# sweet_sixteen_v24_3.net
KiCad netlist of a schematic drawn in EAGLE
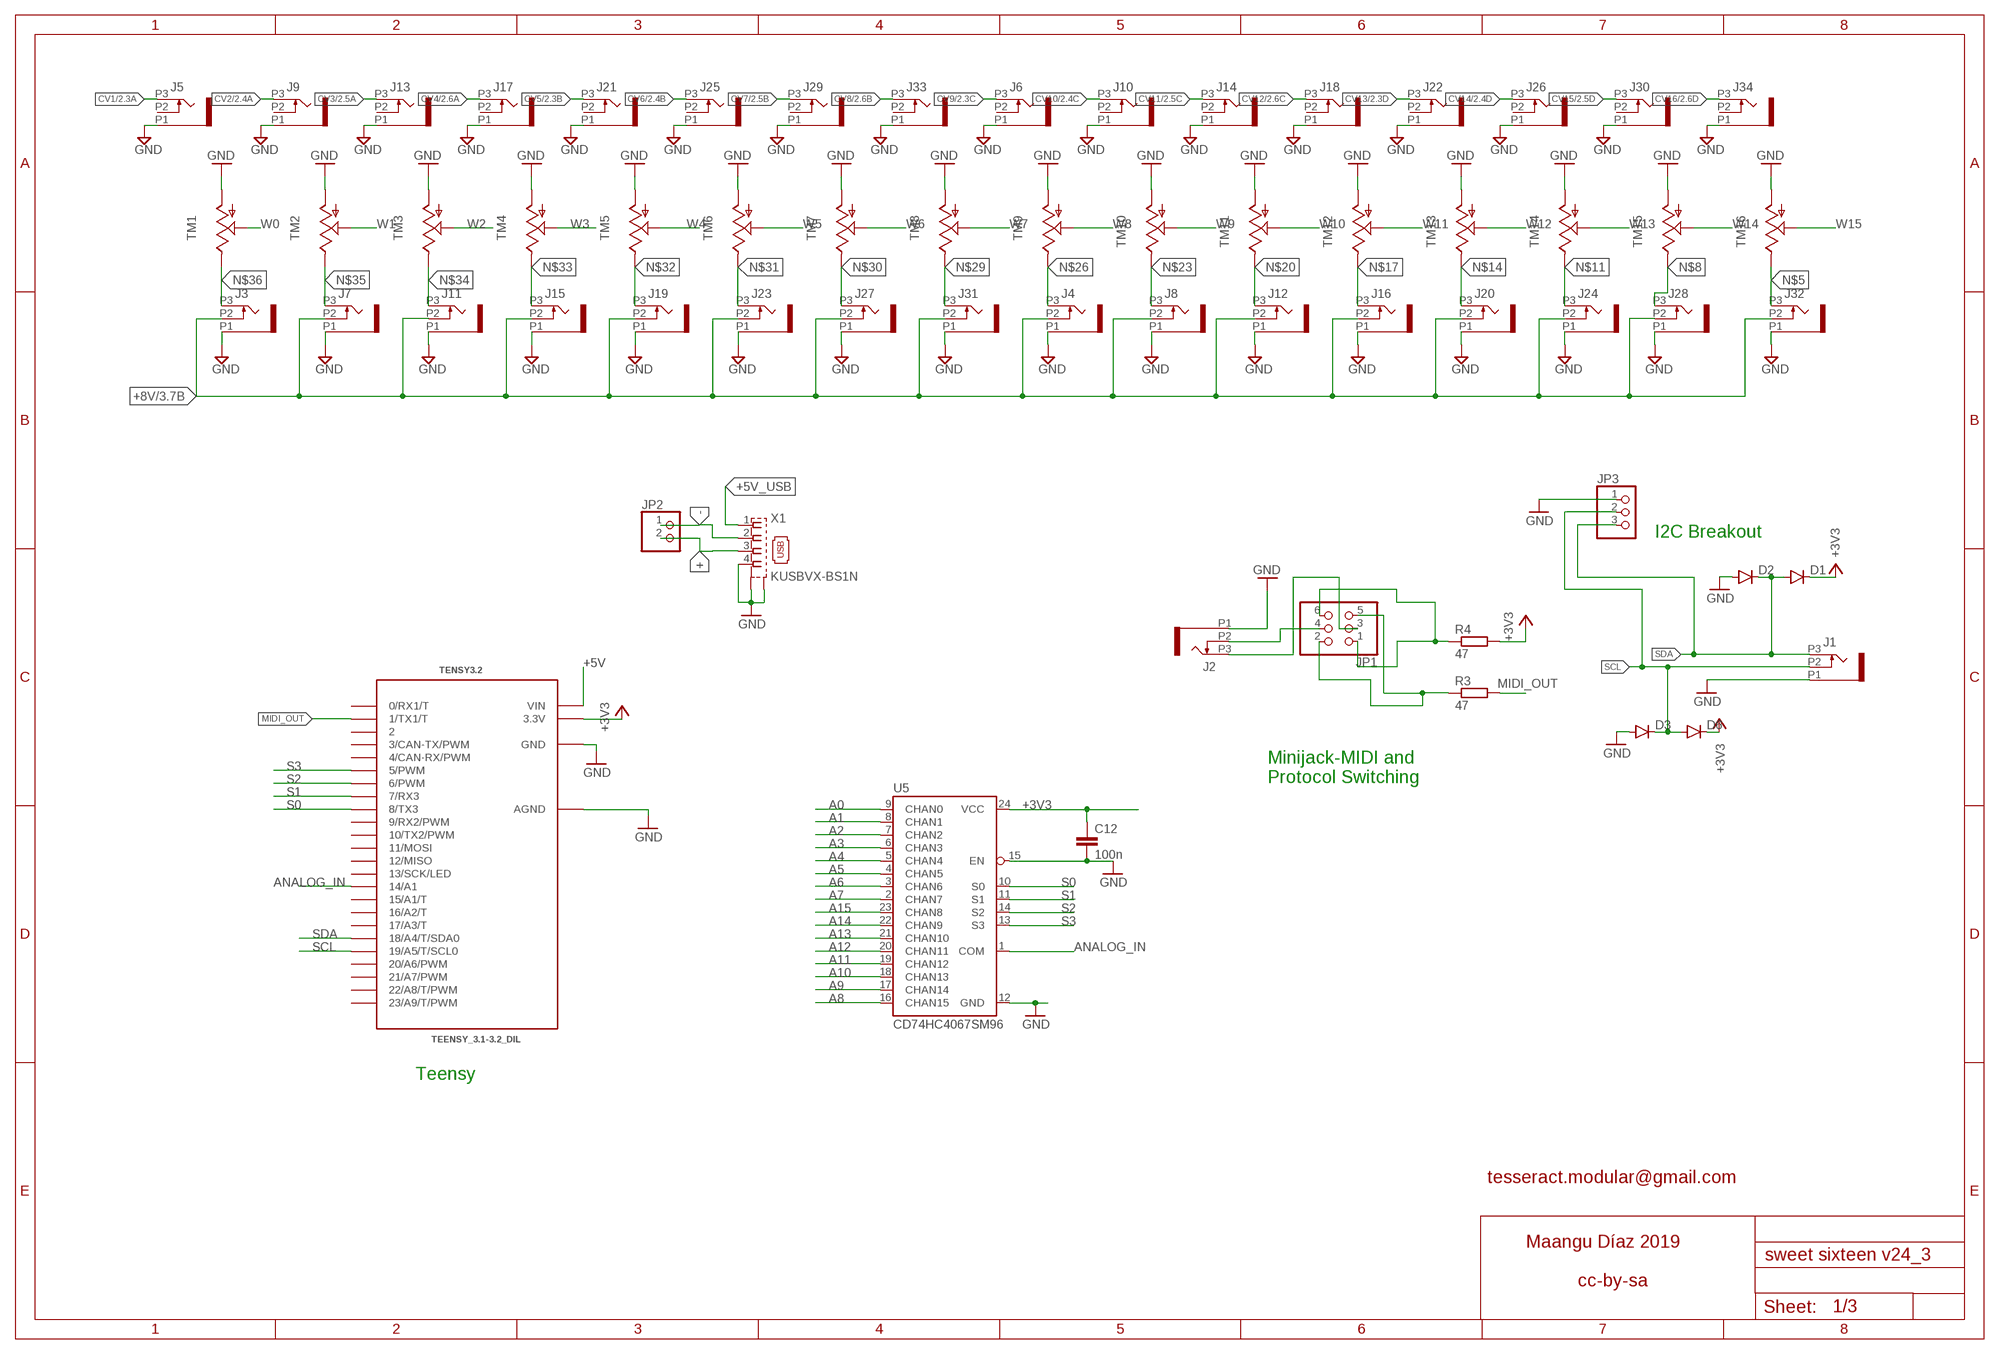
[diagram p0: schematic, sheet 1]
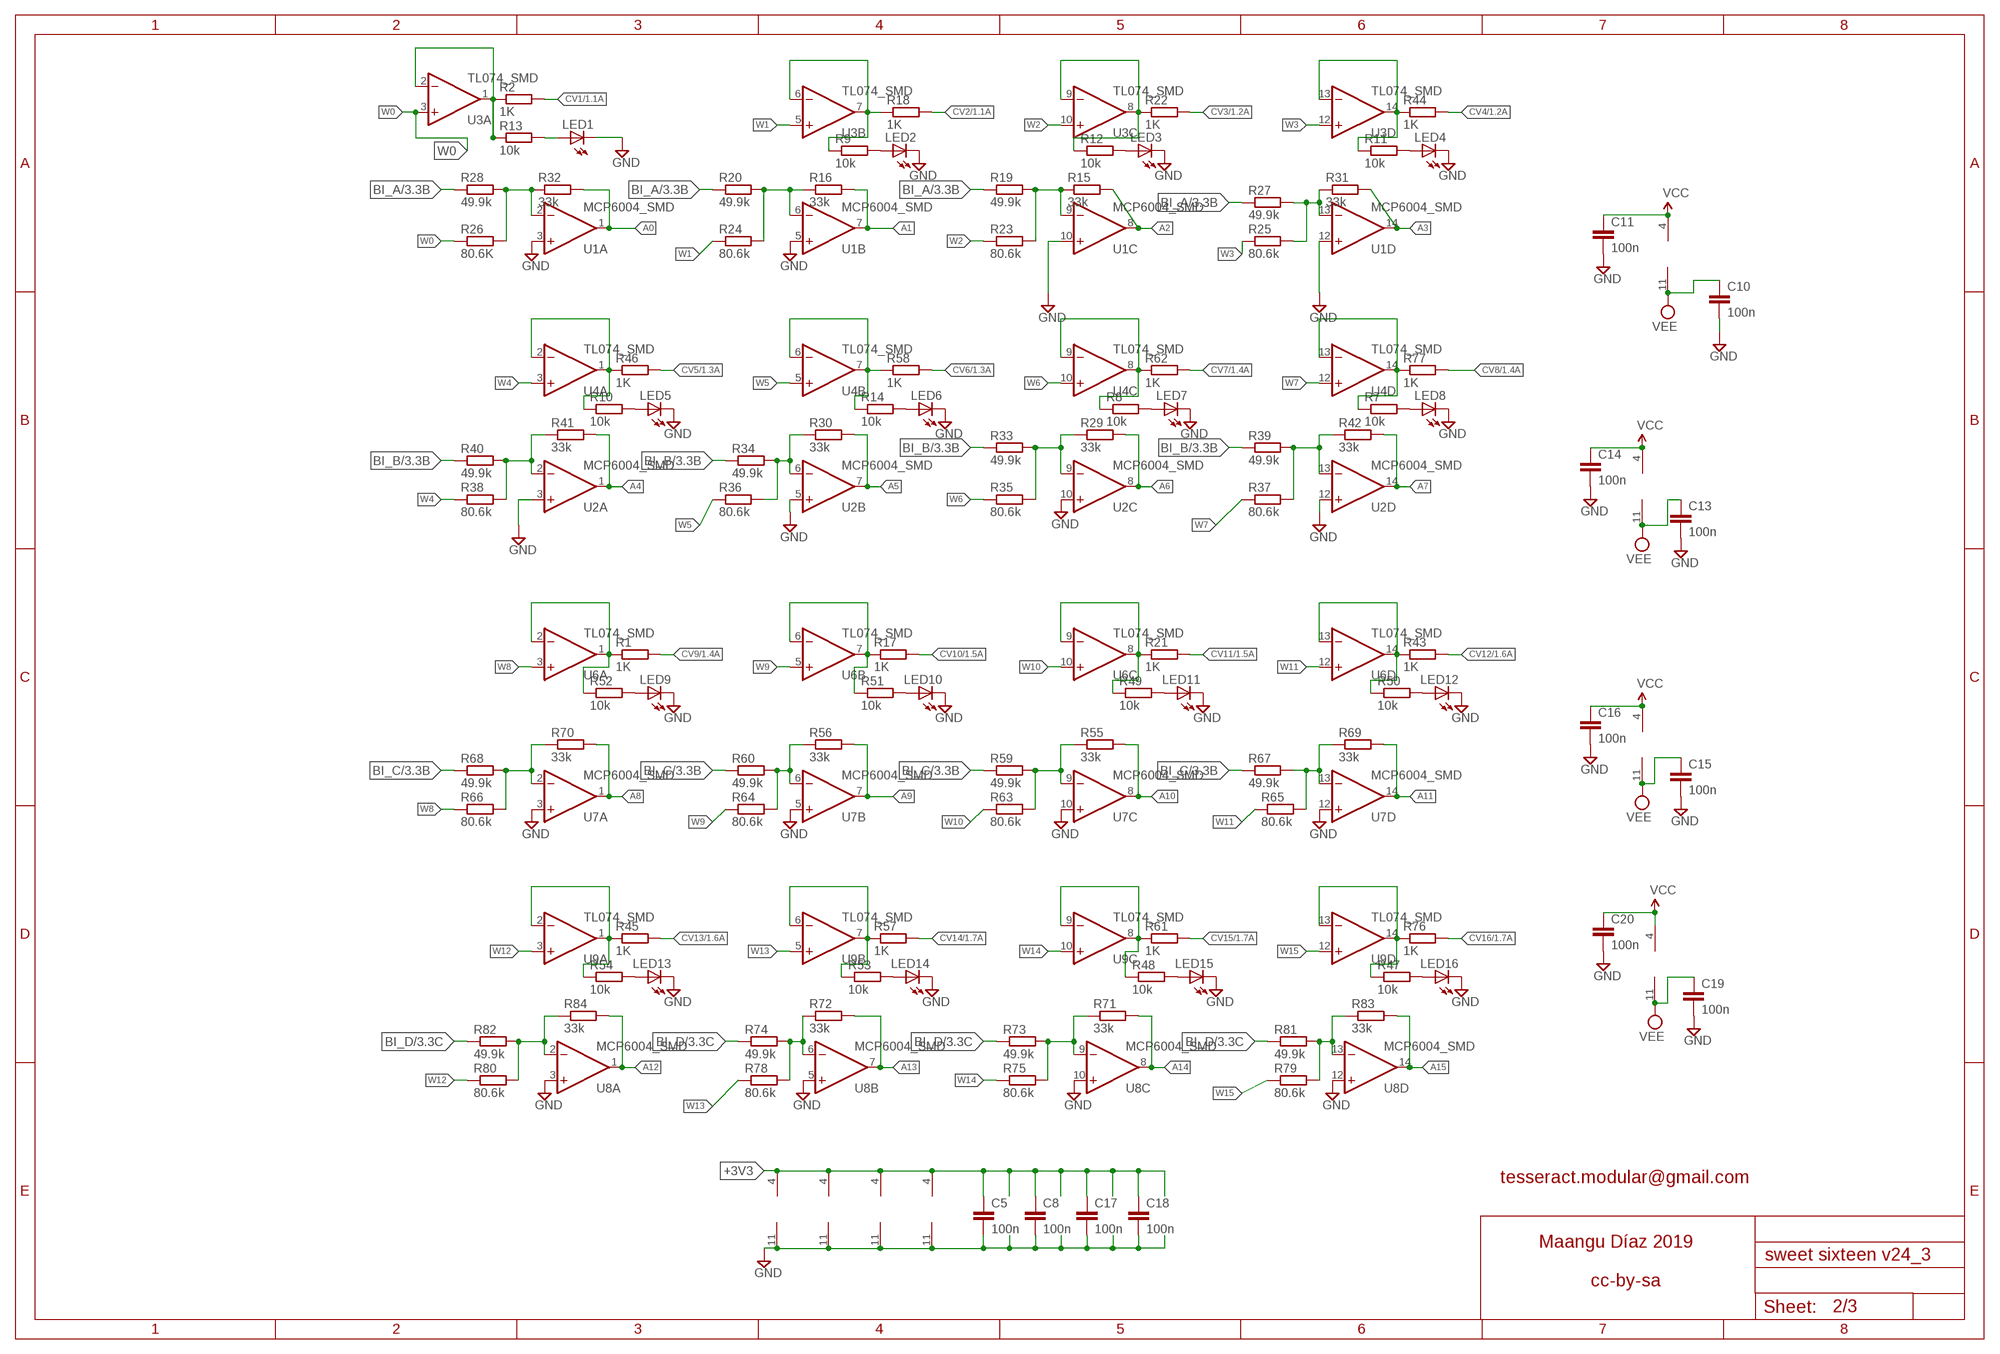
[diagram p1: schematic, sheet 2]
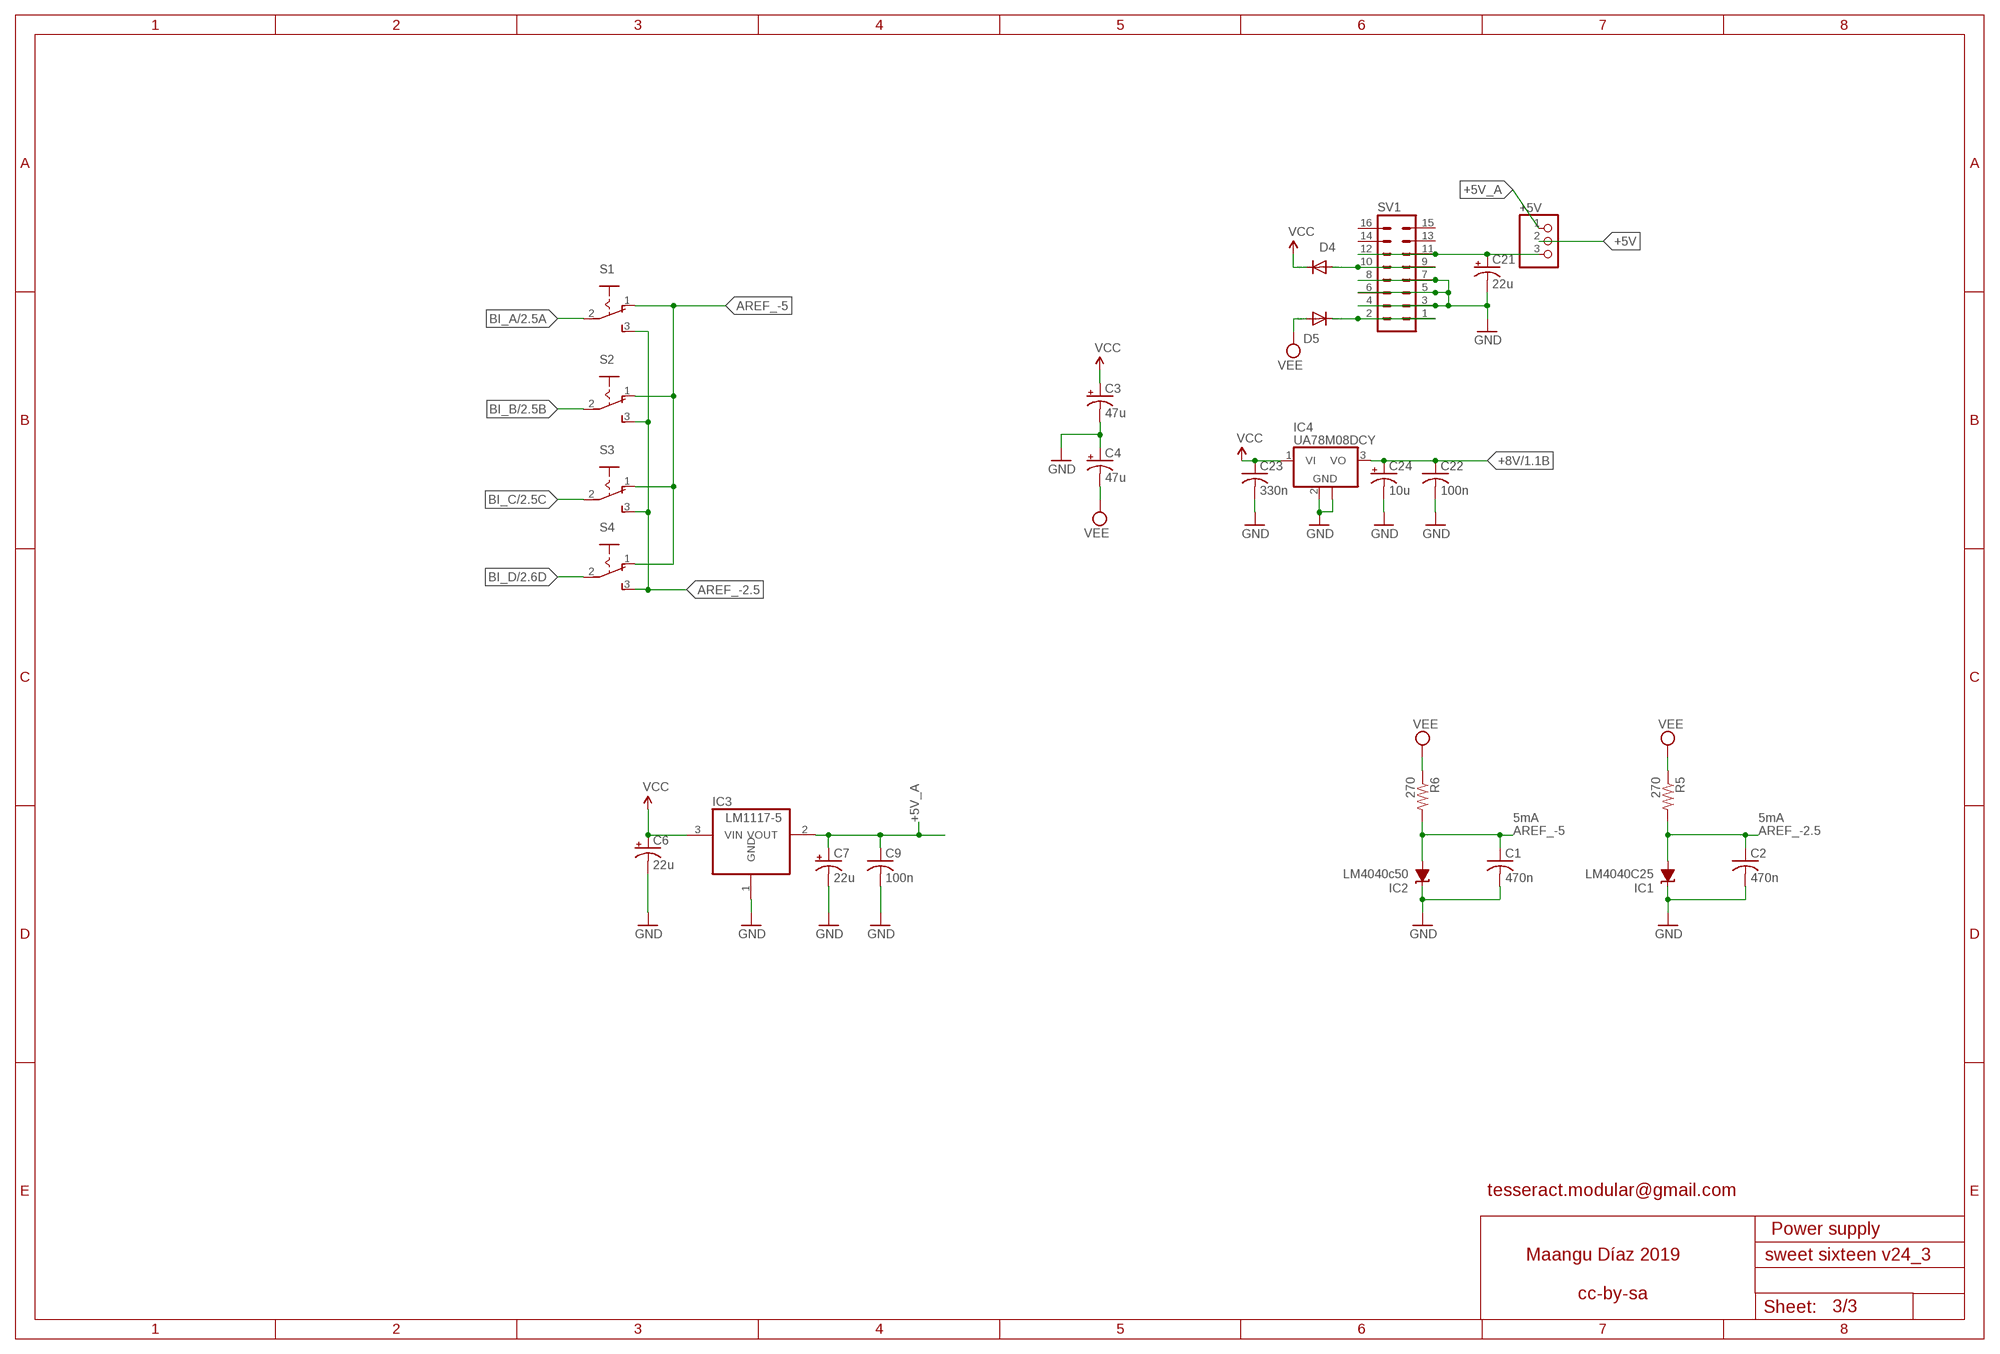
[diagram p2: schematic, sheet 3]

(export (version "E")
  (design (tool "Eeschema 10.0.6"))
  (components
    (comp (ref "+5V")
      (value "PINHD-1X3")
      (footprint "eagle-import:1X03")
      (libsource (lib "eagle-import") (part "PINHD-1X3"))
    )
    (comp (ref "C1")
      (value "470n")
      (footprint "eagle-import:C0603")
      (libsource (lib "eagle-import") (part "C-USC0603"))
    )
    (comp (ref "C2")
      (value "470n")
      (footprint "eagle-import:C0603")
      (libsource (lib "eagle-import") (part "C-USC0603"))
    )
    (comp (ref "C3")
      (value "47u")
      (footprint "eagle-import:PANASONIC_D")
      (libsource (lib "eagle-import") (part "CPOL-USD"))
    )
    (comp (ref "C4")
      (value "47u")
      (footprint "eagle-import:PANASONIC_D")
      (libsource (lib "eagle-import") (part "CPOL-USD"))
    )
    (comp (ref "C6")
      (value "22u")
      (footprint "eagle-import:PANASONIC_D")
      (libsource (lib "eagle-import") (part "CPOL-USD"))
    )
    (comp (ref "C7")
      (value "22u")
      (footprint "eagle-import:PANASONIC_D")
      (libsource (lib "eagle-import") (part "CPOL-USD"))
    )
    (comp (ref "C9")
      (value "100n")
      (footprint "eagle-import:C0603")
      (libsource (lib "eagle-import") (part "C-USC0603"))
    )
    (comp (ref "C21")
      (value "22u")
      (footprint "eagle-import:PANASONIC_D")
      (libsource (lib "eagle-import") (part "CPOL-USD"))
    )
    (comp (ref "C22")
      (value "100n")
      (footprint "eagle-import:C0603")
      (libsource (lib "eagle-import") (part "C-USC0603"))
    )
    (comp (ref "C23")
      (value "330n")
      (footprint "eagle-import:C0603")
      (libsource (lib "eagle-import") (part "C-USC0603"))
    )
    (comp (ref "C24")
      (value "10u")
      (footprint "eagle-import:PANASONIC_C")
      (libsource (lib "eagle-import") (part "CPOL-USC"))
    )
    (comp (ref "D4")
      (value "1N5819HW")
      (footprint "eagle-import:SOD123")
      (libsource (lib "eagle-import") (part "DIODE-SOD123"))
    )
    (comp (ref "D5")
      (value "1N5819HW")
      (footprint "eagle-import:SOD123")
      (libsource (lib "eagle-import") (part "DIODE-SOD123"))
    )
    (comp (ref "IC1")
      (value "LM4040C25")
      (footprint "eagle-import:DBZ_R-PDSO-G3")
      (fields (field (name "MPN") "LM4041B12IDBZR"))
      (libsource (lib "eagle-import") (part "LM4041DBZB12"))
    )
    (comp (ref "IC2")
      (value "LM4040c50")
      (footprint "eagle-import:DBZ_R-PDSO-G3")
      (fields (field (name "MPN") "LM4041B12IDBZR"))
      (libsource (lib "eagle-import") (part "LM4041DBZB12"))
    )
    (comp (ref "IC3")
      (value "LM1117-5")
      (footprint "eagle-import:SOT223")
      (libsource (lib "eagle-import") (part "REG1117"))
    )
    (comp (ref "IC4")
      (value "UA78M08DCY")
      (footprint "eagle-import:SOT223")
      (libsource (lib "eagle-import") (part "UA78MDCY08"))
    )
    (comp (ref "R5")
      (value "270")
      (footprint "eagle-import:R0603")
      (libsource (lib "eagle-import") (part "R-US_R0603"))
    )
    (comp (ref "R6")
      (value "270")
      (footprint "eagle-import:R0603")
      (libsource (lib "eagle-import") (part "R-US_R0603"))
    )
    (comp (ref "S1")
      (value "255SB-MANGURRIN")
      (footprint "eagle-import:255SB_MANGU")
      (libsource (lib "eagle-import") (part "255SB-MANGURRIN"))
    )
    (comp (ref "S2")
      (value "255SB-MANGURRIN")
      (footprint "eagle-import:255SB_MANGU")
      (libsource (lib "eagle-import") (part "255SB-MANGURRIN"))
    )
    (comp (ref "S3")
      (value "255SB-MANGURRIN")
      (footprint "eagle-import:255SB_MANGU")
      (libsource (lib "eagle-import") (part "255SB-MANGURRIN"))
    )
    (comp (ref "S4")
      (value "255SB-MANGURRIN")
      (footprint "eagle-import:255SB_MANGU")
      (libsource (lib "eagle-import") (part "255SB-MANGURRIN"))
    )
    (comp (ref "SV1")
      (value "ML16")
      (footprint "eagle-import:ML16")
      (libsource (lib "eagle-import") (part "ML16"))
    )
    (comp (ref "C12")
      (value "100n")
      (footprint "eagle-import:C0603")
      (libsource (lib "eagle-import") (part "C-EUC0603"))
    )
    (comp (ref "D1")
      (value "DIODESOD123")
      (footprint "eagle-import:SOD-123")
      (libsource (lib "eagle-import") (part "DIODESOD123"))
    )
    (comp (ref "D2")
      (value "DIODESOD123")
      (footprint "eagle-import:SOD-123")
      (libsource (lib "eagle-import") (part "DIODESOD123"))
    )
    (comp (ref "D3")
      (value "DIODESOD123")
      (footprint "eagle-import:SOD-123")
      (libsource (lib "eagle-import") (part "DIODESOD123"))
    )
    (comp (ref "D6")
      (value "DIODESOD123")
      (footprint "eagle-import:SOD-123")
      (libsource (lib "eagle-import") (part "DIODESOD123"))
    )
    (comp (ref "J1")
      (value "PJ301_THONKICONN6")
      (footprint "eagle-import:WQP_PJ_301M6")
      (libsource (lib "eagle-import") (part "PJ301_THONKICONN6"))
    )
    (comp (ref "J2")
      (value "PJ301_THONKICONN6")
      (footprint "eagle-import:WQP_PJ_301M6")
      (libsource (lib "eagle-import") (part "PJ301_THONKICONN6"))
    )
    (comp (ref "J3")
      (value "PJ301_THONKICONN6")
      (footprint "eagle-import:WQP_PJ_301M6")
      (libsource (lib "eagle-import") (part "PJ301_THONKICONN6"))
    )
    (comp (ref "J4")
      (value "PJ301_THONKICONN6")
      (footprint "eagle-import:WQP_PJ_301M6")
      (libsource (lib "eagle-import") (part "PJ301_THONKICONN6"))
    )
    (comp (ref "J5")
      (value "PJ301_THONKICONN6")
      (footprint "eagle-import:WQP_PJ_301M6")
      (libsource (lib "eagle-import") (part "PJ301_THONKICONN6"))
    )
    (comp (ref "J6")
      (value "PJ301_THONKICONN6")
      (footprint "eagle-import:WQP_PJ_301M6")
      (libsource (lib "eagle-import") (part "PJ301_THONKICONN6"))
    )
    (comp (ref "J7")
      (value "PJ301_THONKICONN6")
      (footprint "eagle-import:WQP_PJ_301M6")
      (libsource (lib "eagle-import") (part "PJ301_THONKICONN6"))
    )
    (comp (ref "J8")
      (value "PJ301_THONKICONN6")
      (footprint "eagle-import:WQP_PJ_301M6")
      (libsource (lib "eagle-import") (part "PJ301_THONKICONN6"))
    )
    (comp (ref "J9")
      (value "PJ301_THONKICONN6")
      (footprint "eagle-import:WQP_PJ_301M6")
      (libsource (lib "eagle-import") (part "PJ301_THONKICONN6"))
    )
    (comp (ref "J10")
      (value "PJ301_THONKICONN6")
      (footprint "eagle-import:WQP_PJ_301M6")
      (libsource (lib "eagle-import") (part "PJ301_THONKICONN6"))
    )
    (comp (ref "J11")
      (value "PJ301_THONKICONN6")
      (footprint "eagle-import:WQP_PJ_301M6")
      (libsource (lib "eagle-import") (part "PJ301_THONKICONN6"))
    )
    (comp (ref "J12")
      (value "PJ301_THONKICONN6")
      (footprint "eagle-import:WQP_PJ_301M6")
      (libsource (lib "eagle-import") (part "PJ301_THONKICONN6"))
    )
    (comp (ref "J13")
      (value "PJ301_THONKICONN6")
      (footprint "eagle-import:WQP_PJ_301M6")
      (libsource (lib "eagle-import") (part "PJ301_THONKICONN6"))
    )
    (comp (ref "J14")
      (value "PJ301_THONKICONN6")
      (footprint "eagle-import:WQP_PJ_301M6")
      (libsource (lib "eagle-import") (part "PJ301_THONKICONN6"))
    )
    (comp (ref "J15")
      (value "PJ301_THONKICONN6")
      (footprint "eagle-import:WQP_PJ_301M6")
      (libsource (lib "eagle-import") (part "PJ301_THONKICONN6"))
    )
    (comp (ref "J16")
      (value "PJ301_THONKICONN6")
      (footprint "eagle-import:WQP_PJ_301M6")
      (libsource (lib "eagle-import") (part "PJ301_THONKICONN6"))
    )
    (comp (ref "J17")
      (value "PJ301_THONKICONN6")
      (footprint "eagle-import:WQP_PJ_301M6")
      (libsource (lib "eagle-import") (part "PJ301_THONKICONN6"))
    )
    (comp (ref "J18")
      (value "PJ301_THONKICONN6")
      (footprint "eagle-import:WQP_PJ_301M6")
      (libsource (lib "eagle-import") (part "PJ301_THONKICONN6"))
    )
    (comp (ref "J19")
      (value "PJ301_THONKICONN6")
      (footprint "eagle-import:WQP_PJ_301M6")
      (libsource (lib "eagle-import") (part "PJ301_THONKICONN6"))
    )
    (comp (ref "J20")
      (value "PJ301_THONKICONN6")
      (footprint "eagle-import:WQP_PJ_301M6")
      (libsource (lib "eagle-import") (part "PJ301_THONKICONN6"))
    )
    (comp (ref "J21")
      (value "PJ301_THONKICONN6")
      (footprint "eagle-import:WQP_PJ_301M6")
      (libsource (lib "eagle-import") (part "PJ301_THONKICONN6"))
    )
    (comp (ref "J22")
      (value "PJ301_THONKICONN6")
      (footprint "eagle-import:WQP_PJ_301M6")
      (libsource (lib "eagle-import") (part "PJ301_THONKICONN6"))
    )
    (comp (ref "J23")
      (value "PJ301_THONKICONN6")
      (footprint "eagle-import:WQP_PJ_301M6")
      (libsource (lib "eagle-import") (part "PJ301_THONKICONN6"))
    )
    (comp (ref "J24")
      (value "PJ301_THONKICONN6")
      (footprint "eagle-import:WQP_PJ_301M6")
      (libsource (lib "eagle-import") (part "PJ301_THONKICONN6"))
    )
    (comp (ref "J25")
      (value "PJ301_THONKICONN6")
      (footprint "eagle-import:WQP_PJ_301M6")
      (libsource (lib "eagle-import") (part "PJ301_THONKICONN6"))
    )
    (comp (ref "J26")
      (value "PJ301_THONKICONN6")
      (footprint "eagle-import:WQP_PJ_301M6")
      (libsource (lib "eagle-import") (part "PJ301_THONKICONN6"))
    )
    (comp (ref "J27")
      (value "PJ301_THONKICONN6")
      (footprint "eagle-import:WQP_PJ_301M6")
      (libsource (lib "eagle-import") (part "PJ301_THONKICONN6"))
    )
    (comp (ref "J28")
      (value "PJ301_THONKICONN6")
      (footprint "eagle-import:WQP_PJ_301M6")
      (libsource (lib "eagle-import") (part "PJ301_THONKICONN6"))
    )
    (comp (ref "J29")
      (value "PJ301_THONKICONN6")
      (footprint "eagle-import:WQP_PJ_301M6")
      (libsource (lib "eagle-import") (part "PJ301_THONKICONN6"))
    )
    (comp (ref "J30")
      (value "PJ301_THONKICONN6")
      (footprint "eagle-import:WQP_PJ_301M6")
      (libsource (lib "eagle-import") (part "PJ301_THONKICONN6"))
    )
    (comp (ref "J31")
      (value "PJ301_THONKICONN6")
      (footprint "eagle-import:WQP_PJ_301M6")
      (libsource (lib "eagle-import") (part "PJ301_THONKICONN6"))
    )
    (comp (ref "J32")
      (value "PJ301_THONKICONN6")
      (footprint "eagle-import:WQP_PJ_301M6")
      (libsource (lib "eagle-import") (part "PJ301_THONKICONN6"))
    )
    (comp (ref "J33")
      (value "PJ301_THONKICONN6")
      (footprint "eagle-import:WQP_PJ_301M6")
      (libsource (lib "eagle-import") (part "PJ301_THONKICONN6"))
    )
    (comp (ref "J34")
      (value "PJ301_THONKICONN6")
      (footprint "eagle-import:WQP_PJ_301M6")
      (libsource (lib "eagle-import") (part "PJ301_THONKICONN6"))
    )
    (comp (ref "JP1")
      (value "PINHD-2X3")
      (footprint "eagle-import:2X03")
      (libsource (lib "eagle-import") (part "PINHD-2X3"))
    )
    (comp (ref "JP2")
      (value "PINHD-1X2")
      (footprint "eagle-import:1X02")
      (libsource (lib "eagle-import") (part "PINHD-1X2"))
    )
    (comp (ref "JP3")
      (value "PINHD-1X3")
      (footprint "eagle-import:1X03")
      (libsource (lib "eagle-import") (part "PINHD-1X3"))
    )
    (comp (ref "R3")
      (value "47")
      (footprint "eagle-import:R0805")
      (libsource (lib "eagle-import") (part "R-EU_R0805"))
    )
    (comp (ref "R4")
      (value "47")
      (footprint "eagle-import:R0805")
      (libsource (lib "eagle-import") (part "R-EU_R0805"))
    )
    (comp (ref "TENSY3.2")
      (value "TEENSY_3.1-3.2_DIL")
      (footprint "eagle-import:TEENSY_3.0-3.2&LC_DIL")
      (libsource (lib "eagle-import") (part "TEENSY_3.1-3.2_DIL"))
    )
    (comp (ref "TM1")
      (value "TRIMSLIDE45")
      (footprint "eagle-import:SLIDEPOT-45")
      (libsource (lib "eagle-import") (part "TRIMSLIDE45"))
    )
    (comp (ref "TM2")
      (value "TRIMSLIDE45")
      (footprint "eagle-import:SLIDEPOT-45")
      (libsource (lib "eagle-import") (part "TRIMSLIDE45"))
    )
    (comp (ref "TM3")
      (value "TRIMSLIDE45")
      (footprint "eagle-import:SLIDEPOT-45")
      (libsource (lib "eagle-import") (part "TRIMSLIDE45"))
    )
    (comp (ref "TM4")
      (value "TRIMSLIDE45")
      (footprint "eagle-import:SLIDEPOT-45")
      (libsource (lib "eagle-import") (part "TRIMSLIDE45"))
    )
    (comp (ref "TM5")
      (value "TRIMSLIDE45")
      (footprint "eagle-import:SLIDEPOT-45")
      (libsource (lib "eagle-import") (part "TRIMSLIDE45"))
    )
    (comp (ref "TM6")
      (value "TRIMSLIDE45")
      (footprint "eagle-import:SLIDEPOT-45")
      (libsource (lib "eagle-import") (part "TRIMSLIDE45"))
    )
    (comp (ref "TM7")
      (value "TRIMSLIDE45")
      (footprint "eagle-import:SLIDEPOT-45")
      (libsource (lib "eagle-import") (part "TRIMSLIDE45"))
    )
    (comp (ref "TM8")
      (value "TRIMSLIDE45")
      (footprint "eagle-import:SLIDEPOT-45")
      (libsource (lib "eagle-import") (part "TRIMSLIDE45"))
    )
    (comp (ref "TM9")
      (value "TRIMSLIDE45")
      (footprint "eagle-import:SLIDEPOT-45")
      (libsource (lib "eagle-import") (part "TRIMSLIDE45"))
    )
    (comp (ref "TM10")
      (value "TRIMSLIDE45")
      (footprint "eagle-import:SLIDEPOT-45")
      (libsource (lib "eagle-import") (part "TRIMSLIDE45"))
    )
    (comp (ref "TM11")
      (value "TRIMSLIDE45")
      (footprint "eagle-import:SLIDEPOT-45")
      (libsource (lib "eagle-import") (part "TRIMSLIDE45"))
    )
    (comp (ref "TM12")
      (value "TRIMSLIDE45")
      (footprint "eagle-import:SLIDEPOT-45")
      (libsource (lib "eagle-import") (part "TRIMSLIDE45"))
    )
    (comp (ref "TM13")
      (value "TRIMSLIDE45")
      (footprint "eagle-import:SLIDEPOT-45")
      (libsource (lib "eagle-import") (part "TRIMSLIDE45"))
    )
    (comp (ref "TM14")
      (value "TRIMSLIDE45")
      (footprint "eagle-import:SLIDEPOT-45")
      (libsource (lib "eagle-import") (part "TRIMSLIDE45"))
    )
    (comp (ref "TM15")
      (value "TRIMSLIDE45")
      (footprint "eagle-import:SLIDEPOT-45")
      (libsource (lib "eagle-import") (part "TRIMSLIDE45"))
    )
    (comp (ref "TM16")
      (value "TRIMSLIDE45")
      (footprint "eagle-import:SLIDEPOT-45")
      (libsource (lib "eagle-import") (part "TRIMSLIDE45"))
    )
    (comp (ref "U5")
      (value "CD74HC4067SM96")
      (footprint "eagle-import:SOIC127P1030X265-24")
      (libsource (lib "eagle-import") (part "744067SO24"))
    )
    (comp (ref "X1")
      (value "KUSBVX-BS1N")
      (footprint "eagle-import:KUSBVX-BS1N")
      (libsource (lib "eagle-import") (part "KUSBVX-BS1N"))
    )
    (comp (ref "C5")
      (value "100n")
      (footprint "eagle-import:C0603")
      (libsource (lib "eagle-import") (part "C-EUC0603"))
    )
    (comp (ref "C8")
      (value "100n")
      (footprint "eagle-import:C0603K")
      (libsource (lib "eagle-import") (part "C-EUC0603K"))
    )
    (comp (ref "C10")
      (value "100n")
      (footprint "eagle-import:C0603")
      (libsource (lib "eagle-import") (part "C-EUC0603"))
    )
    (comp (ref "C11")
      (value "100n")
      (footprint "eagle-import:C0603")
      (libsource (lib "eagle-import") (part "C-EUC0603"))
    )
    (comp (ref "C13")
      (value "100n")
      (footprint "eagle-import:C0603")
      (libsource (lib "eagle-import") (part "C-EUC0603"))
    )
    (comp (ref "C14")
      (value "100n")
      (footprint "eagle-import:C0603")
      (libsource (lib "eagle-import") (part "C-EUC0603"))
    )
    (comp (ref "C15")
      (value "100n")
      (footprint "eagle-import:C0603")
      (libsource (lib "eagle-import") (part "C-EUC0603"))
    )
    (comp (ref "C16")
      (value "100n")
      (footprint "eagle-import:C0603")
      (libsource (lib "eagle-import") (part "C-EUC0603"))
    )
    (comp (ref "C17")
      (value "100n")
      (footprint "eagle-import:C0603K")
      (libsource (lib "eagle-import") (part "C-EUC0603K"))
    )
    (comp (ref "C18")
      (value "100n")
      (footprint "eagle-import:C0603")
      (libsource (lib "eagle-import") (part "C-EUC0603"))
    )
    (comp (ref "C19")
      (value "100n")
      (footprint "eagle-import:C0603")
      (libsource (lib "eagle-import") (part "C-EUC0603"))
    )
    (comp (ref "C20")
      (value "100n")
      (footprint "eagle-import:C0603")
      (libsource (lib "eagle-import") (part "C-EUC0603"))
    )
    (comp (ref "LED1")
      (value "LED3MM")
      (footprint "eagle-import:LED3MM")
      (libsource (lib "eagle-import") (part "LED3MM"))
    )
    (comp (ref "LED2")
      (value "LED3MM")
      (footprint "eagle-import:LED3MM")
      (libsource (lib "eagle-import") (part "LED3MM"))
    )
    (comp (ref "LED3")
      (value "LED3MM")
      (footprint "eagle-import:LED3MM")
      (libsource (lib "eagle-import") (part "LED3MM"))
    )
    (comp (ref "LED4")
      (value "LED3MM")
      (footprint "eagle-import:LED3MM")
      (libsource (lib "eagle-import") (part "LED3MM"))
    )
    (comp (ref "LED5")
      (value "LED3MM")
      (footprint "eagle-import:LED3MM")
      (libsource (lib "eagle-import") (part "LED3MM"))
    )
    (comp (ref "LED6")
      (value "LED3MM")
      (footprint "eagle-import:LED3MM")
      (libsource (lib "eagle-import") (part "LED3MM"))
    )
    (comp (ref "LED7")
      (value "LED3MM")
      (footprint "eagle-import:LED3MM")
      (libsource (lib "eagle-import") (part "LED3MM"))
    )
    (comp (ref "LED8")
      (value "LED3MM")
      (footprint "eagle-import:LED3MM")
      (libsource (lib "eagle-import") (part "LED3MM"))
    )
    (comp (ref "LED9")
      (value "LED3MM")
      (footprint "eagle-import:LED3MM")
      (libsource (lib "eagle-import") (part "LED3MM"))
    )
    (comp (ref "LED10")
      (value "LED3MM")
      (footprint "eagle-import:LED3MM")
      (libsource (lib "eagle-import") (part "LED3MM"))
    )
    (comp (ref "LED11")
      (value "LED3MM")
      (footprint "eagle-import:LED3MM")
      (libsource (lib "eagle-import") (part "LED3MM"))
    )
    (comp (ref "LED12")
      (value "LED3MM")
      (footprint "eagle-import:LED3MM")
      (libsource (lib "eagle-import") (part "LED3MM"))
    )
    (comp (ref "LED13")
      (value "LED3MM")
      (footprint "eagle-import:LED3MM")
      (libsource (lib "eagle-import") (part "LED3MM"))
    )
    (comp (ref "LED14")
      (value "LED3MM")
      (footprint "eagle-import:LED3MM")
      (libsource (lib "eagle-import") (part "LED3MM"))
    )
    (comp (ref "LED15")
      (value "LED3MM")
      (footprint "eagle-import:LED3MM")
      (libsource (lib "eagle-import") (part "LED3MM"))
    )
    (comp (ref "LED16")
      (value "LED3MM")
      (footprint "eagle-import:LED3MM")
      (libsource (lib "eagle-import") (part "LED3MM"))
    )
    (comp (ref "R1")
      (value "1K")
      (footprint "eagle-import:R0603")
      (libsource (lib "eagle-import") (part "R-EU_R0603"))
    )
    (comp (ref "R2")
      (value "1K")
      (footprint "eagle-import:R0603")
      (libsource (lib "eagle-import") (part "R-EU_R0603"))
    )
    (comp (ref "R7")
      (value "10k")
      (footprint "eagle-import:R0603")
      (libsource (lib "eagle-import") (part "R-EU_R0603"))
    )
    (comp (ref "R8")
      (value "10k")
      (footprint "eagle-import:R0603")
      (libsource (lib "eagle-import") (part "R-EU_R0603"))
    )
    (comp (ref "R9")
      (value "10k")
      (footprint "eagle-import:R0603")
      (libsource (lib "eagle-import") (part "R-EU_R0603"))
    )
    (comp (ref "R10")
      (value "10k")
      (footprint "eagle-import:R0603")
      (libsource (lib "eagle-import") (part "R-EU_R0603"))
    )
    (comp (ref "R11")
      (value "10k")
      (footprint "eagle-import:R0603")
      (libsource (lib "eagle-import") (part "R-EU_R0603"))
    )
    (comp (ref "R12")
      (value "10k")
      (footprint "eagle-import:R0603")
      (libsource (lib "eagle-import") (part "R-EU_R0603"))
    )
    (comp (ref "R13")
      (value "10k")
      (footprint "eagle-import:R0603")
      (libsource (lib "eagle-import") (part "R-EU_R0603"))
    )
    (comp (ref "R14")
      (value "10k")
      (footprint "eagle-import:R0603")
      (libsource (lib "eagle-import") (part "R-EU_R0603"))
    )
    (comp (ref "R15")
      (value "33k")
      (footprint "eagle-import:R0603")
      (libsource (lib "eagle-import") (part "R-EU_R0603"))
    )
    (comp (ref "R16")
      (value "33k")
      (footprint "eagle-import:R0603")
      (libsource (lib "eagle-import") (part "R-EU_R0603"))
    )
    (comp (ref "R17")
      (value "1K")
      (footprint "eagle-import:R0603")
      (libsource (lib "eagle-import") (part "R-EU_R0603"))
    )
    (comp (ref "R18")
      (value "1K")
      (footprint "eagle-import:R0603")
      (libsource (lib "eagle-import") (part "R-EU_R0603"))
    )
    (comp (ref "R19")
      (value "49.9k")
      (footprint "eagle-import:R0603")
      (libsource (lib "eagle-import") (part "R-EU_R0603"))
    )
    (comp (ref "R20")
      (value "49.9k")
      (footprint "eagle-import:R0603")
      (libsource (lib "eagle-import") (part "R-EU_R0603"))
    )
    (comp (ref "R21")
      (value "1K")
      (footprint "eagle-import:R0603")
      (libsource (lib "eagle-import") (part "R-EU_R0603"))
    )
    (comp (ref "R22")
      (value "1K")
      (footprint "eagle-import:R0603")
      (libsource (lib "eagle-import") (part "R-EU_R0603"))
    )
    (comp (ref "R23")
      (value "80.6k")
      (footprint "eagle-import:R0603")
      (libsource (lib "eagle-import") (part "R-EU_R0603"))
    )
    (comp (ref "R24")
      (value "80.6k")
      (footprint "eagle-import:R0603")
      (libsource (lib "eagle-import") (part "R-EU_R0603"))
    )
    (comp (ref "R25")
      (value "80.6k")
      (footprint "eagle-import:R0603")
      (libsource (lib "eagle-import") (part "R-EU_R0603"))
    )
    (comp (ref "R26")
      (value "80.6K")
      (footprint "eagle-import:R0603")
      (libsource (lib "eagle-import") (part "R-EU_R0603"))
    )
    (comp (ref "R27")
      (value "49.9k")
      (footprint "eagle-import:R0603")
      (libsource (lib "eagle-import") (part "R-EU_R0603"))
    )
    (comp (ref "R28")
      (value "49.9k")
      (footprint "eagle-import:R0603")
      (libsource (lib "eagle-import") (part "R-EU_R0603"))
    )
    (comp (ref "R29")
      (value "33k")
      (footprint "eagle-import:R0603")
      (libsource (lib "eagle-import") (part "R-EU_R0603"))
    )
    (comp (ref "R30")
      (value "33k")
      (footprint "eagle-import:R0603")
      (libsource (lib "eagle-import") (part "R-EU_R0603"))
    )
    (comp (ref "R31")
      (value "33k")
      (footprint "eagle-import:R0603")
      (libsource (lib "eagle-import") (part "R-EU_R0603"))
    )
    (comp (ref "R32")
      (value "33k")
      (footprint "eagle-import:R0603")
      (libsource (lib "eagle-import") (part "R-EU_R0603"))
    )
    (comp (ref "R33")
      (value "49.9k")
      (footprint "eagle-import:R0603")
      (libsource (lib "eagle-import") (part "R-EU_R0603"))
    )
    (comp (ref "R34")
      (value "49.9k")
      (footprint "eagle-import:R0603")
      (libsource (lib "eagle-import") (part "R-EU_R0603"))
    )
    (comp (ref "R35")
      (value "80.6k")
      (footprint "eagle-import:R0603")
      (libsource (lib "eagle-import") (part "R-EU_R0603"))
    )
    (comp (ref "R36")
      (value "80.6k")
      (footprint "eagle-import:R0603")
      (libsource (lib "eagle-import") (part "R-EU_R0603"))
    )
    (comp (ref "R37")
      (value "80.6k")
      (footprint "eagle-import:R0603")
      (libsource (lib "eagle-import") (part "R-EU_R0603"))
    )
    (comp (ref "R38")
      (value "80.6k")
      (footprint "eagle-import:R0603")
      (libsource (lib "eagle-import") (part "R-EU_R0603"))
    )
    (comp (ref "R39")
      (value "49.9k")
      (footprint "eagle-import:R0603")
      (libsource (lib "eagle-import") (part "R-EU_R0603"))
    )
    (comp (ref "R40")
      (value "49.9k")
      (footprint "eagle-import:R0603")
      (libsource (lib "eagle-import") (part "R-EU_R0603"))
    )
    (comp (ref "R41")
      (value "33k")
      (footprint "eagle-import:R0603")
      (libsource (lib "eagle-import") (part "R-EU_R0603"))
    )
    (comp (ref "R42")
      (value "33k")
      (footprint "eagle-import:R0603")
      (libsource (lib "eagle-import") (part "R-EU_R0603"))
    )
    (comp (ref "R43")
      (value "1K")
      (footprint "eagle-import:R0603")
      (libsource (lib "eagle-import") (part "R-EU_R0603"))
    )
    (comp (ref "R44")
      (value "1K")
      (footprint "eagle-import:R0603")
      (libsource (lib "eagle-import") (part "R-EU_R0603"))
    )
    (comp (ref "R45")
      (value "1K")
      (footprint "eagle-import:R0603")
      (libsource (lib "eagle-import") (part "R-EU_R0603"))
    )
    (comp (ref "R46")
      (value "1K")
      (footprint "eagle-import:R0603")
      (libsource (lib "eagle-import") (part "R-EU_R0603"))
    )
    (comp (ref "R47")
      (value "10k")
      (footprint "eagle-import:R0603")
      (libsource (lib "eagle-import") (part "R-EU_R0603"))
    )
    (comp (ref "R48")
      (value "10k")
      (footprint "eagle-import:R0603")
      (libsource (lib "eagle-import") (part "R-EU_R0603"))
    )
    (comp (ref "R49")
      (value "10k")
      (footprint "eagle-import:R0603")
      (libsource (lib "eagle-import") (part "R-EU_R0603"))
    )
    (comp (ref "R50")
      (value "10k")
      (footprint "eagle-import:R0603")
      (libsource (lib "eagle-import") (part "R-EU_R0603"))
    )
    (comp (ref "R51")
      (value "10k")
      (footprint "eagle-import:R0603")
      (libsource (lib "eagle-import") (part "R-EU_R0603"))
    )
    (comp (ref "R52")
      (value "10k")
      (footprint "eagle-import:R0603")
      (libsource (lib "eagle-import") (part "R-EU_R0603"))
    )
    (comp (ref "R53")
      (value "10k")
      (footprint "eagle-import:R0603")
      (libsource (lib "eagle-import") (part "R-EU_R0603"))
    )
    (comp (ref "R54")
      (value "10k")
      (footprint "eagle-import:R0603")
      (libsource (lib "eagle-import") (part "R-EU_R0603"))
    )
    (comp (ref "R55")
      (value "33k")
      (footprint "eagle-import:R0603")
      (libsource (lib "eagle-import") (part "R-EU_R0603"))
    )
    (comp (ref "R56")
      (value "33k")
      (footprint "eagle-import:R0603")
      (libsource (lib "eagle-import") (part "R-EU_R0603"))
    )
    (comp (ref "R57")
      (value "1K")
      (footprint "eagle-import:R0603")
      (libsource (lib "eagle-import") (part "R-EU_R0603"))
    )
    (comp (ref "R58")
      (value "1K")
      (footprint "eagle-import:R0603")
      (libsource (lib "eagle-import") (part "R-EU_R0603"))
    )
    (comp (ref "R59")
      (value "49.9k")
      (footprint "eagle-import:R0603")
      (libsource (lib "eagle-import") (part "R-EU_R0603"))
    )
    (comp (ref "R60")
      (value "49.9k")
      (footprint "eagle-import:R0603")
      (libsource (lib "eagle-import") (part "R-EU_R0603"))
    )
    (comp (ref "R61")
      (value "1K")
      (footprint "eagle-import:R0603")
      (libsource (lib "eagle-import") (part "R-EU_R0603"))
    )
    (comp (ref "R62")
      (value "1K")
      (footprint "eagle-import:R0603")
      (libsource (lib "eagle-import") (part "R-EU_R0603"))
    )
    (comp (ref "R63")
      (value "80.6k")
      (footprint "eagle-import:R0603")
      (libsource (lib "eagle-import") (part "R-EU_R0603"))
    )
    (comp (ref "R64")
      (value "80.6k")
      (footprint "eagle-import:R0603")
      (libsource (lib "eagle-import") (part "R-EU_R0603"))
    )
    (comp (ref "R65")
      (value "80.6k")
      (footprint "eagle-import:R0603")
      (libsource (lib "eagle-import") (part "R-EU_R0603"))
    )
    (comp (ref "R66")
      (value "80.6k")
      (footprint "eagle-import:R0603")
      (libsource (lib "eagle-import") (part "R-EU_R0603"))
    )
    (comp (ref "R67")
      (value "49.9k")
      (footprint "eagle-import:R0603")
      (libsource (lib "eagle-import") (part "R-EU_R0603"))
    )
    (comp (ref "R68")
      (value "49.9k")
      (footprint "eagle-import:R0603")
      (libsource (lib "eagle-import") (part "R-EU_R0603"))
    )
    (comp (ref "R69")
      (value "33k")
      (footprint "eagle-import:R0603")
      (libsource (lib "eagle-import") (part "R-EU_R0603"))
    )
    (comp (ref "R70")
      (value "33k")
      (footprint "eagle-import:R0603")
      (libsource (lib "eagle-import") (part "R-EU_R0603"))
    )
    (comp (ref "R71")
      (value "33k")
      (footprint "eagle-import:R0603")
      (libsource (lib "eagle-import") (part "R-EU_R0603"))
    )
    (comp (ref "R72")
      (value "33k")
      (footprint "eagle-import:R0603")
      (libsource (lib "eagle-import") (part "R-EU_R0603"))
    )
    (comp (ref "R73")
      (value "49.9k")
      (footprint "eagle-import:R0603")
      (libsource (lib "eagle-import") (part "R-EU_R0603"))
    )
    (comp (ref "R74")
      (value "49.9k")
      (footprint "eagle-import:R0603")
      (libsource (lib "eagle-import") (part "R-EU_R0603"))
    )
    (comp (ref "R75")
      (value "80.6k")
      (footprint "eagle-import:R0603")
      (libsource (lib "eagle-import") (part "R-EU_R0603"))
    )
    (comp (ref "R76")
      (value "1K")
      (footprint "eagle-import:R0603")
      (libsource (lib "eagle-import") (part "R-EU_R0603"))
    )
    (comp (ref "R77")
      (value "1K")
      (footprint "eagle-import:R0603")
      (libsource (lib "eagle-import") (part "R-EU_R0603"))
    )
    (comp (ref "R78")
      (value "80.6k")
      (footprint "eagle-import:R0603")
      (libsource (lib "eagle-import") (part "R-EU_R0603"))
    )
    (comp (ref "R79")
      (value "80.6k")
      (footprint "eagle-import:R0603")
      (libsource (lib "eagle-import") (part "R-EU_R0603"))
    )
    (comp (ref "R80")
      (value "80.6k")
      (footprint "eagle-import:R0603")
      (libsource (lib "eagle-import") (part "R-EU_R0603"))
    )
    (comp (ref "R81")
      (value "49.9k")
      (footprint "eagle-import:R0603")
      (libsource (lib "eagle-import") (part "R-EU_R0603"))
    )
    (comp (ref "R82")
      (value "49.9k")
      (footprint "eagle-import:R0603")
      (libsource (lib "eagle-import") (part "R-EU_R0603"))
    )
    (comp (ref "R83")
      (value "33k")
      (footprint "eagle-import:R0603")
      (libsource (lib "eagle-import") (part "R-EU_R0603"))
    )
    (comp (ref "R84")
      (value "33k")
      (footprint "eagle-import:R0603")
      (libsource (lib "eagle-import") (part "R-EU_R0603"))
    )
    (comp (ref "U1")
      (value "MCP6004_SMD")
      (footprint "eagle-import:SO14")
      (libsource (lib "eagle-import") (part "MCP6004_SMD"))
    )
    (comp (ref "U2")
      (value "MCP6004_SMD")
      (footprint "eagle-import:SO14")
      (libsource (lib "eagle-import") (part "MCP6004_SMD"))
    )
    (comp (ref "U3")
      (value "TL074_SMD")
      (footprint "eagle-import:SO14")
      (libsource (lib "eagle-import") (part "TL074_SMD"))
    )
    (comp (ref "U4")
      (value "TL074_SMD")
      (footprint "eagle-import:SO14")
      (libsource (lib "eagle-import") (part "TL074_SMD"))
    )
    (comp (ref "U6")
      (value "TL074_SMD")
      (footprint "eagle-import:SO14")
      (libsource (lib "eagle-import") (part "TL074_SMD"))
    )
    (comp (ref "U7")
      (value "MCP6004_SMD")
      (footprint "eagle-import:SO14")
      (libsource (lib "eagle-import") (part "MCP6004_SMD"))
    )
    (comp (ref "U8")
      (value "MCP6004_SMD")
      (footprint "eagle-import:SO14")
      (libsource (lib "eagle-import") (part "MCP6004_SMD"))
    )
    (comp (ref "U9")
      (value "TL074_SMD")
      (footprint "eagle-import:SO14")
      (libsource (lib "eagle-import") (part "TL074_SMD"))
    )
  )
  (nets
    (net (code "1") (name "+") (class "Default")
      (node (ref "JP2") (pin "2") (pinfunction "2_2") (pintype "passive"))
      (node (ref "X1") (pin "3") (pinfunction "3_3") (pintype "passive"))
    )
    (net (code "2") (name "+3V3") (class "Default")
      (node (ref "C12") (pin "1") (pinfunction "1_1") (pintype "passive"))
      (node (ref "C17") (pin "1") (pinfunction "1_1") (pintype "passive"))
      (node (ref "C18") (pin "1") (pinfunction "1_1") (pintype "passive"))
      (node (ref "C5") (pin "1") (pinfunction "1_1") (pintype "passive"))
      (node (ref "C8") (pin "1") (pinfunction "1_1") (pintype "passive"))
      (node (ref "D1") (pin "C") (pinfunction "C_C") (pintype "passive"))
      (node (ref "D6") (pin "C") (pinfunction "C_C") (pintype "passive"))
      (node (ref "R4") (pin "2") (pinfunction "2_2") (pintype "passive"))
      (node (ref "TENSY3.2") (pin "3.3V") (pinfunction "3.3V_3.3V") (pintype "power_in"))
      (node (ref "U1") (pin "4") (pinfunction "V+_4") (pintype "power_in"))
      (node (ref "U2") (pin "4") (pinfunction "V+_4") (pintype "power_in"))
      (node (ref "U5") (pin "24") (pinfunction "VCC_24") (pintype "bidirectional"))
      (node (ref "U7") (pin "4") (pinfunction "V+_4") (pintype "power_in"))
      (node (ref "U8") (pin "4") (pinfunction "V+_4") (pintype "power_in"))
    )
    (net (code "3") (name "+5V") (class "Default")
      (node (ref "+5V") (pin "2") (pinfunction "2_2") (pintype "passive"))
      (node (ref "TENSY3.2") (pin "VIN") (pinfunction "VIN_VIN") (pintype "power_in"))
    )
    (net (code "4") (name "+5V_A") (class "Default")
      (node (ref "+5V") (pin "1") (pinfunction "1_1") (pintype "passive"))
      (node (ref "C7") (pin "+") (pinfunction "+_+") (pintype "passive"))
      (node (ref "C9") (pin "1") (pinfunction "1_1") (pintype "passive"))
      (node (ref "IC3") (pin "2") (pinfunction "VOUT_2") (pintype "output"))
    )
    (net (code "5") (name "+5V_USB") (class "Default")
      (node (ref "X1") (pin "1") (pinfunction "1_1") (pintype "passive"))
    )
    (net (code "6") (name "+8V") (class "Default")
      (node (ref "C22") (pin "1") (pinfunction "1_1") (pintype "passive"))
      (node (ref "C24") (pin "+") (pinfunction "+_+") (pintype "passive"))
      (node (ref "IC4") (pin "3") (pinfunction "VO_3") (pintype "passive"))
      (node (ref "J11") (pin "P2") (pinfunction "2_P2") (pintype "passive"))
      (node (ref "J12") (pin "P2") (pinfunction "2_P2") (pintype "passive"))
      (node (ref "J15") (pin "P2") (pinfunction "2_P2") (pintype "passive"))
      (node (ref "J16") (pin "P2") (pinfunction "2_P2") (pintype "passive"))
      (node (ref "J19") (pin "P2") (pinfunction "2_P2") (pintype "passive"))
      (node (ref "J20") (pin "P2") (pinfunction "2_P2") (pintype "passive"))
      (node (ref "J23") (pin "P2") (pinfunction "2_P2") (pintype "passive"))
      (node (ref "J24") (pin "P2") (pinfunction "2_P2") (pintype "passive"))
      (node (ref "J27") (pin "P2") (pinfunction "2_P2") (pintype "passive"))
      (node (ref "J28") (pin "P2") (pinfunction "2_P2") (pintype "passive"))
      (node (ref "J3") (pin "P2") (pinfunction "2_P2") (pintype "passive"))
      (node (ref "J31") (pin "P2") (pinfunction "2_P2") (pintype "passive"))
      (node (ref "J32") (pin "P2") (pinfunction "2_P2") (pintype "passive"))
      (node (ref "J4") (pin "P2") (pinfunction "2_P2") (pintype "passive"))
      (node (ref "J7") (pin "P2") (pinfunction "2_P2") (pintype "passive"))
      (node (ref "J8") (pin "P2") (pinfunction "2_P2") (pintype "passive"))
    )
    (net (code "7") (name "-") (class "Default")
      (node (ref "JP2") (pin "1") (pinfunction "1_1") (pintype "passive"))
      (node (ref "X1") (pin "2") (pinfunction "2_2") (pintype "passive"))
    )
    (net (code "8") (name "A0") (class "Default")
      (node (ref "R32") (pin "2") (pinfunction "2_2") (pintype "passive"))
      (node (ref "U1") (pin "1") (pinfunction "OUT_1") (pintype "output"))
      (node (ref "U5") (pin "9") (pinfunction "CHAN0_9") (pintype "bidirectional"))
    )
    (net (code "9") (name "A1") (class "Default")
      (node (ref "R16") (pin "2") (pinfunction "2_2") (pintype "passive"))
      (node (ref "U1") (pin "7") (pinfunction "OUT_7") (pintype "output"))
      (node (ref "U5") (pin "8") (pinfunction "CHAN1_8") (pintype "bidirectional"))
    )
    (net (code "10") (name "A2") (class "Default")
      (node (ref "R15") (pin "2") (pinfunction "2_2") (pintype "passive"))
      (node (ref "U1") (pin "8") (pinfunction "OUT_8") (pintype "output"))
      (node (ref "U5") (pin "7") (pinfunction "CHAN2_7") (pintype "bidirectional"))
    )
    (net (code "11") (name "A3") (class "Default")
      (node (ref "R31") (pin "2") (pinfunction "2_2") (pintype "passive"))
      (node (ref "U1") (pin "14") (pinfunction "OUT_14") (pintype "output"))
      (node (ref "U5") (pin "6") (pinfunction "CHAN3_6") (pintype "bidirectional"))
    )
    (net (code "12") (name "A4") (class "Default")
      (node (ref "R41") (pin "2") (pinfunction "2_2") (pintype "passive"))
      (node (ref "U2") (pin "1") (pinfunction "OUT_1") (pintype "output"))
      (node (ref "U5") (pin "5") (pinfunction "CHAN4_5") (pintype "bidirectional"))
    )
    (net (code "13") (name "A5") (class "Default")
      (node (ref "R30") (pin "2") (pinfunction "2_2") (pintype "passive"))
      (node (ref "U2") (pin "7") (pinfunction "OUT_7") (pintype "output"))
      (node (ref "U5") (pin "4") (pinfunction "CHAN5_4") (pintype "bidirectional"))
    )
    (net (code "14") (name "A6") (class "Default")
      (node (ref "R29") (pin "2") (pinfunction "2_2") (pintype "passive"))
      (node (ref "U2") (pin "8") (pinfunction "OUT_8") (pintype "output"))
      (node (ref "U5") (pin "3") (pinfunction "CHAN6_3") (pintype "bidirectional"))
    )
    (net (code "15") (name "A7") (class "Default")
      (node (ref "R42") (pin "2") (pinfunction "2_2") (pintype "passive"))
      (node (ref "U2") (pin "14") (pinfunction "OUT_14") (pintype "output"))
      (node (ref "U5") (pin "2") (pinfunction "CHAN7_2") (pintype "bidirectional"))
    )
    (net (code "16") (name "A8") (class "Default")
      (node (ref "R70") (pin "2") (pinfunction "2_2") (pintype "passive"))
      (node (ref "U5") (pin "16") (pinfunction "CHAN15_16") (pintype "bidirectional"))
      (node (ref "U7") (pin "1") (pinfunction "OUT_1") (pintype "output"))
    )
    (net (code "17") (name "A9") (class "Default")
      (node (ref "R56") (pin "2") (pinfunction "2_2") (pintype "passive"))
      (node (ref "U5") (pin "17") (pinfunction "CHAN14_17") (pintype "bidirectional"))
      (node (ref "U7") (pin "7") (pinfunction "OUT_7") (pintype "output"))
    )
    (net (code "18") (name "A10") (class "Default")
      (node (ref "R55") (pin "2") (pinfunction "2_2") (pintype "passive"))
      (node (ref "U5") (pin "18") (pinfunction "CHAN13_18") (pintype "bidirectional"))
      (node (ref "U7") (pin "8") (pinfunction "OUT_8") (pintype "output"))
    )
    (net (code "19") (name "A11") (class "Default")
      (node (ref "R69") (pin "2") (pinfunction "2_2") (pintype "passive"))
      (node (ref "U5") (pin "19") (pinfunction "CHAN12_19") (pintype "bidirectional"))
      (node (ref "U7") (pin "14") (pinfunction "OUT_14") (pintype "output"))
    )
    (net (code "20") (name "A12") (class "Default")
      (node (ref "R84") (pin "2") (pinfunction "2_2") (pintype "passive"))
      (node (ref "U5") (pin "20") (pinfunction "CHAN11_20") (pintype "bidirectional"))
      (node (ref "U8") (pin "1") (pinfunction "OUT_1") (pintype "output"))
    )
    (net (code "21") (name "A13") (class "Default")
      (node (ref "R72") (pin "2") (pinfunction "2_2") (pintype "passive"))
      (node (ref "U5") (pin "21") (pinfunction "CHAN10_21") (pintype "bidirectional"))
      (node (ref "U8") (pin "7") (pinfunction "OUT_7") (pintype "output"))
    )
    (net (code "22") (name "A14") (class "Default")
      (node (ref "R71") (pin "2") (pinfunction "2_2") (pintype "passive"))
      (node (ref "U5") (pin "22") (pinfunction "CHAN9_22") (pintype "bidirectional"))
      (node (ref "U8") (pin "8") (pinfunction "OUT_8") (pintype "output"))
    )
    (net (code "23") (name "A15") (class "Default")
      (node (ref "R83") (pin "2") (pinfunction "2_2") (pintype "passive"))
      (node (ref "U5") (pin "23") (pinfunction "CHAN8_23") (pintype "bidirectional"))
      (node (ref "U8") (pin "14") (pinfunction "OUT_14") (pintype "output"))
    )
    (net (code "24") (name "ANALOG_IN") (class "Default")
      (node (ref "TENSY3.2") (pin "14/A0") (pinfunction "14/A1_14/A0") (pintype "bidirectional"))
      (node (ref "U5") (pin "1") (pinfunction "COM_1") (pintype "bidirectional"))
    )
    (net (code "25") (name "AREF_-2.5") (class "Default")
      (node (ref "C2") (pin "1") (pinfunction "1_1") (pintype "passive"))
      (node (ref "IC1") (pin "2") (pinfunction "A_2") (pintype "passive"))
      (node (ref "R5") (pin "2") (pinfunction "2_2") (pintype "passive"))
      (node (ref "S1") (pin "3") (pinfunction "S_3") (pintype "passive"))
      (node (ref "S2") (pin "3") (pinfunction "S_3") (pintype "passive"))
      (node (ref "S3") (pin "3") (pinfunction "S_3") (pintype "passive"))
      (node (ref "S4") (pin "3") (pinfunction "S_3") (pintype "passive"))
    )
    (net (code "26") (name "AREF_-5") (class "Default")
      (node (ref "C1") (pin "1") (pinfunction "1_1") (pintype "passive"))
      (node (ref "IC2") (pin "2") (pinfunction "A_2") (pintype "passive"))
      (node (ref "R6") (pin "2") (pinfunction "2_2") (pintype "passive"))
      (node (ref "S1") (pin "1") (pinfunction "O_1") (pintype "passive"))
      (node (ref "S2") (pin "1") (pinfunction "O_1") (pintype "passive"))
      (node (ref "S3") (pin "1") (pinfunction "O_1") (pintype "passive"))
      (node (ref "S4") (pin "1") (pinfunction "O_1") (pintype "passive"))
    )
    (net (code "27") (name "BI_A") (class "Default")
      (node (ref "R19") (pin "1") (pinfunction "1_1") (pintype "passive"))
      (node (ref "R20") (pin "1") (pinfunction "1_1") (pintype "passive"))
      (node (ref "R27") (pin "1") (pinfunction "1_1") (pintype "passive"))
      (node (ref "R28") (pin "1") (pinfunction "1_1") (pintype "passive"))
      (node (ref "S1") (pin "2") (pinfunction "P_2") (pintype "passive"))
    )
    (net (code "28") (name "BI_B") (class "Default")
      (node (ref "R33") (pin "1") (pinfunction "1_1") (pintype "passive"))
      (node (ref "R34") (pin "1") (pinfunction "1_1") (pintype "passive"))
      (node (ref "R39") (pin "1") (pinfunction "1_1") (pintype "passive"))
      (node (ref "R40") (pin "1") (pinfunction "1_1") (pintype "passive"))
      (node (ref "S2") (pin "2") (pinfunction "P_2") (pintype "passive"))
    )
    (net (code "29") (name "BI_C") (class "Default")
      (node (ref "R59") (pin "1") (pinfunction "1_1") (pintype "passive"))
      (node (ref "R60") (pin "1") (pinfunction "1_1") (pintype "passive"))
      (node (ref "R67") (pin "1") (pinfunction "1_1") (pintype "passive"))
      (node (ref "R68") (pin "1") (pinfunction "1_1") (pintype "passive"))
      (node (ref "S3") (pin "2") (pinfunction "P_2") (pintype "passive"))
    )
    (net (code "30") (name "BI_D") (class "Default")
      (node (ref "R73") (pin "1") (pinfunction "1_1") (pintype "passive"))
      (node (ref "R74") (pin "1") (pinfunction "1_1") (pintype "passive"))
      (node (ref "R81") (pin "1") (pinfunction "1_1") (pintype "passive"))
      (node (ref "R82") (pin "1") (pinfunction "1_1") (pintype "passive"))
      (node (ref "S4") (pin "2") (pinfunction "P_2") (pintype "passive"))
    )
    (net (code "31") (name "CV1") (class "Default")
      (node (ref "J5") (pin "P3") (pinfunction "3_P3") (pintype "passive"))
      (node (ref "R2") (pin "2") (pinfunction "2_2") (pintype "passive"))
    )
    (net (code "32") (name "CV2") (class "Default")
      (node (ref "J9") (pin "P3") (pinfunction "3_P3") (pintype "passive"))
      (node (ref "R18") (pin "2") (pinfunction "2_2") (pintype "passive"))
    )
    (net (code "33") (name "CV3") (class "Default")
      (node (ref "J13") (pin "P3") (pinfunction "3_P3") (pintype "passive"))
      (node (ref "R22") (pin "2") (pinfunction "2_2") (pintype "passive"))
    )
    (net (code "34") (name "CV4") (class "Default")
      (node (ref "J17") (pin "P3") (pinfunction "3_P3") (pintype "passive"))
      (node (ref "R44") (pin "2") (pinfunction "2_2") (pintype "passive"))
    )
    (net (code "35") (name "CV5") (class "Default")
      (node (ref "J21") (pin "P3") (pinfunction "3_P3") (pintype "passive"))
      (node (ref "R46") (pin "2") (pinfunction "2_2") (pintype "passive"))
    )
    (net (code "36") (name "CV6") (class "Default")
      (node (ref "J25") (pin "P3") (pinfunction "3_P3") (pintype "passive"))
      (node (ref "R58") (pin "2") (pinfunction "2_2") (pintype "passive"))
    )
    (net (code "37") (name "CV7") (class "Default")
      (node (ref "J29") (pin "P3") (pinfunction "3_P3") (pintype "passive"))
      (node (ref "R62") (pin "2") (pinfunction "2_2") (pintype "passive"))
    )
    (net (code "38") (name "CV8") (class "Default")
      (node (ref "J33") (pin "P3") (pinfunction "3_P3") (pintype "passive"))
      (node (ref "R77") (pin "2") (pinfunction "2_2") (pintype "passive"))
    )
    (net (code "39") (name "CV9") (class "Default")
      (node (ref "J6") (pin "P3") (pinfunction "3_P3") (pintype "passive"))
      (node (ref "R1") (pin "2") (pinfunction "2_2") (pintype "passive"))
    )
    (net (code "40") (name "CV10") (class "Default")
      (node (ref "J10") (pin "P3") (pinfunction "3_P3") (pintype "passive"))
      (node (ref "R17") (pin "2") (pinfunction "2_2") (pintype "passive"))
    )
    (net (code "41") (name "CV11") (class "Default")
      (node (ref "J14") (pin "P3") (pinfunction "3_P3") (pintype "passive"))
      (node (ref "R21") (pin "2") (pinfunction "2_2") (pintype "passive"))
    )
    (net (code "42") (name "CV12") (class "Default")
      (node (ref "J18") (pin "P3") (pinfunction "3_P3") (pintype "passive"))
      (node (ref "R43") (pin "2") (pinfunction "2_2") (pintype "passive"))
    )
    (net (code "43") (name "CV13") (class "Default")
      (node (ref "J22") (pin "P3") (pinfunction "3_P3") (pintype "passive"))
      (node (ref "R45") (pin "2") (pinfunction "2_2") (pintype "passive"))
    )
    (net (code "44") (name "CV14") (class "Default")
      (node (ref "J26") (pin "P3") (pinfunction "3_P3") (pintype "passive"))
      (node (ref "R57") (pin "2") (pinfunction "2_2") (pintype "passive"))
    )
    (net (code "45") (name "CV15") (class "Default")
      (node (ref "J30") (pin "P3") (pinfunction "3_P3") (pintype "passive"))
      (node (ref "R61") (pin "2") (pinfunction "2_2") (pintype "passive"))
    )
    (net (code "46") (name "CV16") (class "Default")
      (node (ref "J34") (pin "P3") (pinfunction "3_P3") (pintype "passive"))
      (node (ref "R76") (pin "2") (pinfunction "2_2") (pintype "passive"))
    )
    (net (code "47") (name "GND") (class "Default")
      (node (ref "C1") (pin "2") (pinfunction "2_2") (pintype "passive"))
      (node (ref "C10") (pin "2") (pinfunction "2_2") (pintype "passive"))
      (node (ref "C11") (pin "2") (pinfunction "2_2") (pintype "passive"))
      (node (ref "C12") (pin "2") (pinfunction "2_2") (pintype "passive"))
      (node (ref "C13") (pin "2") (pinfunction "2_2") (pintype "passive"))
      (node (ref "C14") (pin "2") (pinfunction "2_2") (pintype "passive"))
      (node (ref "C15") (pin "2") (pinfunction "2_2") (pintype "passive"))
      (node (ref "C16") (pin "2") (pinfunction "2_2") (pintype "passive"))
      (node (ref "C17") (pin "2") (pinfunction "2_2") (pintype "passive"))
      (node (ref "C18") (pin "2") (pinfunction "2_2") (pintype "passive"))
      (node (ref "C19") (pin "2") (pinfunction "2_2") (pintype "passive"))
      (node (ref "C2") (pin "2") (pinfunction "2_2") (pintype "passive"))
      (node (ref "C20") (pin "2") (pinfunction "2_2") (pintype "passive"))
      (node (ref "C21") (pin "-") (pinfunction "-_-") (pintype "passive"))
      (node (ref "C22") (pin "2") (pinfunction "2_2") (pintype "passive"))
      (node (ref "C23") (pin "2") (pinfunction "2_2") (pintype "passive"))
      (node (ref "C24") (pin "-") (pinfunction "-_-") (pintype "passive"))
      (node (ref "C3") (pin "-") (pinfunction "-_-") (pintype "passive"))
      (node (ref "C4") (pin "+") (pinfunction "+_+") (pintype "passive"))
      (node (ref "C5") (pin "2") (pinfunction "2_2") (pintype "passive"))
      (node (ref "C6") (pin "-") (pinfunction "-_-") (pintype "passive"))
      (node (ref "C7") (pin "-") (pinfunction "-_-") (pintype "passive"))
      (node (ref "C8") (pin "2") (pinfunction "2_2") (pintype "passive"))
      (node (ref "C9") (pin "2") (pinfunction "2_2") (pintype "passive"))
      (node (ref "D2") (pin "A") (pinfunction "A_A") (pintype "passive"))
      (node (ref "D3") (pin "A") (pinfunction "A_A") (pintype "passive"))
      (node (ref "IC1") (pin "1") (pinfunction "C_1") (pintype "passive"))
      (node (ref "IC2") (pin "1") (pinfunction "C_1") (pintype "passive"))
      (node (ref "IC3") (pin "1") (pinfunction "GND_1") (pintype "power_in"))
      (node (ref "IC4") (pin "2") (pinfunction "GND_2") (pintype "passive"))
      (node (ref "IC4") (pin "4") (pinfunction "GND_4") (pintype "passive"))
      (node (ref "J1") (pin "P1") (pinfunction "1_P1") (pintype "passive"))
      (node (ref "J10") (pin "P1") (pinfunction "1_P1") (pintype "passive"))
      (node (ref "J11") (pin "P1") (pinfunction "1_P1") (pintype "passive"))
      (node (ref "J12") (pin "P1") (pinfunction "1_P1") (pintype "passive"))
      (node (ref "J13") (pin "P1") (pinfunction "1_P1") (pintype "passive"))
      (node (ref "J14") (pin "P1") (pinfunction "1_P1") (pintype "passive"))
      (node (ref "J15") (pin "P1") (pinfunction "1_P1") (pintype "passive"))
      (node (ref "J16") (pin "P1") (pinfunction "1_P1") (pintype "passive"))
      (node (ref "J17") (pin "P1") (pinfunction "1_P1") (pintype "passive"))
      (node (ref "J18") (pin "P1") (pinfunction "1_P1") (pintype "passive"))
      (node (ref "J19") (pin "P1") (pinfunction "1_P1") (pintype "passive"))
      (node (ref "J2") (pin "P1") (pinfunction "1_P1") (pintype "passive"))
      (node (ref "J20") (pin "P1") (pinfunction "1_P1") (pintype "passive"))
      (node (ref "J21") (pin "P1") (pinfunction "1_P1") (pintype "passive"))
      (node (ref "J22") (pin "P1") (pinfunction "1_P1") (pintype "passive"))
      (node (ref "J23") (pin "P1") (pinfunction "1_P1") (pintype "passive"))
      (node (ref "J24") (pin "P1") (pinfunction "1_P1") (pintype "passive"))
      (node (ref "J25") (pin "P1") (pinfunction "1_P1") (pintype "passive"))
      (node (ref "J26") (pin "P1") (pinfunction "1_P1") (pintype "passive"))
      (node (ref "J27") (pin "P1") (pinfunction "1_P1") (pintype "passive"))
      (node (ref "J28") (pin "P1") (pinfunction "1_P1") (pintype "passive"))
      (node (ref "J29") (pin "P1") (pinfunction "1_P1") (pintype "passive"))
      (node (ref "J3") (pin "P1") (pinfunction "1_P1") (pintype "passive"))
      (node (ref "J30") (pin "P1") (pinfunction "1_P1") (pintype "passive"))
      (node (ref "J31") (pin "P1") (pinfunction "1_P1") (pintype "passive"))
      (node (ref "J32") (pin "P1") (pinfunction "1_P1") (pintype "passive"))
      (node (ref "J33") (pin "P1") (pinfunction "1_P1") (pintype "passive"))
      (node (ref "J34") (pin "P1") (pinfunction "1_P1") (pintype "passive"))
      (node (ref "J4") (pin "P1") (pinfunction "1_P1") (pintype "passive"))
      (node (ref "J5") (pin "P1") (pinfunction "1_P1") (pintype "passive"))
      (node (ref "J6") (pin "P1") (pinfunction "1_P1") (pintype "passive"))
      (node (ref "J7") (pin "P1") (pinfunction "1_P1") (pintype "passive"))
      (node (ref "J8") (pin "P1") (pinfunction "1_P1") (pintype "passive"))
      (node (ref "J9") (pin "P1") (pinfunction "1_P1") (pintype "passive"))
      (node (ref "JP3") (pin "1") (pinfunction "1_1") (pintype "passive"))
      (node (ref "LED1") (pin "K") (pinfunction "C_K") (pintype "passive"))
      (node (ref "LED10") (pin "K") (pinfunction "C_K") (pintype "passive"))
      (node (ref "LED11") (pin "K") (pinfunction "C_K") (pintype "passive"))
      (node (ref "LED12") (pin "K") (pinfunction "C_K") (pintype "passive"))
      (node (ref "LED13") (pin "K") (pinfunction "C_K") (pintype "passive"))
      (node (ref "LED14") (pin "K") (pinfunction "C_K") (pintype "passive"))
      (node (ref "LED15") (pin "K") (pinfunction "C_K") (pintype "passive"))
      (node (ref "LED16") (pin "K") (pinfunction "C_K") (pintype "passive"))
      (node (ref "LED2") (pin "K") (pinfunction "C_K") (pintype "passive"))
      (node (ref "LED3") (pin "K") (pinfunction "C_K") (pintype "passive"))
      (node (ref "LED4") (pin "K") (pinfunction "C_K") (pintype "passive"))
      (node (ref "LED5") (pin "K") (pinfunction "C_K") (pintype "passive"))
      (node (ref "LED6") (pin "K") (pinfunction "C_K") (pintype "passive"))
      (node (ref "LED7") (pin "K") (pinfunction "C_K") (pintype "passive"))
      (node (ref "LED8") (pin "K") (pinfunction "C_K") (pintype "passive"))
      (node (ref "LED9") (pin "K") (pinfunction "C_K") (pintype "passive"))
      (node (ref "SV1") (pin "3") (pinfunction "3_3") (pintype "passive"))
      (node (ref "SV1") (pin "4") (pinfunction "4_4") (pintype "passive"))
      (node (ref "SV1") (pin "5") (pinfunction "5_5") (pintype "passive"))
      (node (ref "SV1") (pin "6") (pinfunction "6_6") (pintype "passive"))
      (node (ref "SV1") (pin "7") (pinfunction "7_7") (pintype "passive"))
      (node (ref "SV1") (pin "8") (pinfunction "8_8") (pintype "passive"))
      (node (ref "TENSY3.2") (pin "AGND") (pinfunction "AGND_AGND") (pintype "power_in"))
      (node (ref "TENSY3.2") (pin "GND") (pinfunction "GND_GND") (pintype "power_in"))
      (node (ref "TM1") (pin "A") (pinfunction "A_A") (pintype "passive"))
      (node (ref "TM10") (pin "A") (pinfunction "A_A") (pintype "passive"))
      (node (ref "TM11") (pin "A") (pinfunction "A_A") (pintype "passive"))
      (node (ref "TM12") (pin "A") (pinfunction "A_A") (pintype "passive"))
      (node (ref "TM13") (pin "A") (pinfunction "A_A") (pintype "passive"))
      (node (ref "TM14") (pin "A") (pinfunction "A_A") (pintype "passive"))
      (node (ref "TM15") (pin "A") (pinfunction "A_A") (pintype "passive"))
      (node (ref "TM16") (pin "A") (pinfunction "A_A") (pintype "passive"))
      (node (ref "TM2") (pin "A") (pinfunction "A_A") (pintype "passive"))
      (node (ref "TM3") (pin "A") (pinfunction "A_A") (pintype "passive"))
      (node (ref "TM4") (pin "A") (pinfunction "A_A") (pintype "passive"))
      (node (ref "TM5") (pin "A") (pinfunction "A_A") (pintype "passive"))
      (node (ref "TM6") (pin "A") (pinfunction "A_A") (pintype "passive"))
      (node (ref "TM7") (pin "A") (pinfunction "A_A") (pintype "passive"))
      (node (ref "TM8") (pin "A") (pinfunction "A_A") (pintype "passive"))
      (node (ref "TM9") (pin "A") (pinfunction "A_A") (pintype "passive"))
      (node (ref "U1") (pin "10") (pinfunction "+IN_10") (pintype "input"))
      (node (ref "U1") (pin "11") (pinfunction "V-_11") (pintype "power_in"))
      (node (ref "U1") (pin "12") (pinfunction "+IN_12") (pintype "input"))
      (node (ref "U1") (pin "3") (pinfunction "+IN_3") (pintype "input"))
      (node (ref "U1") (pin "5") (pinfunction "+IN_5") (pintype "input"))
      (node (ref "U2") (pin "10") (pinfunction "+IN_10") (pintype "input"))
      (node (ref "U2") (pin "11") (pinfunction "V-_11") (pintype "power_in"))
      (node (ref "U2") (pin "12") (pinfunction "+IN_12") (pintype "input"))
      (node (ref "U2") (pin "3") (pinfunction "+IN_3") (pintype "input"))
      (node (ref "U2") (pin "5") (pinfunction "+IN_5") (pintype "input"))
      (node (ref "U5") (pin "12") (pinfunction "GND_12") (pintype "bidirectional"))
      (node (ref "U5") (pin "15") (pinfunction "EN_15") (pintype "input"))
      (node (ref "U7") (pin "10") (pinfunction "+IN_10") (pintype "input"))
      (node (ref "U7") (pin "11") (pinfunction "V-_11") (pintype "power_in"))
      (node (ref "U7") (pin "12") (pinfunction "+IN_12") (pintype "input"))
      (node (ref "U7") (pin "3") (pinfunction "+IN_3") (pintype "input"))
      (node (ref "U7") (pin "5") (pinfunction "+IN_5") (pintype "input"))
      (node (ref "U8") (pin "10") (pinfunction "+IN_10") (pintype "input"))
      (node (ref "U8") (pin "11") (pinfunction "V-_11") (pintype "power_in"))
      (node (ref "U8") (pin "12") (pinfunction "+IN_12") (pintype "input"))
      (node (ref "U8") (pin "3") (pinfunction "+IN_3") (pintype "input"))
      (node (ref "U8") (pin "5") (pinfunction "+IN_5") (pintype "input"))
      (node (ref "X1") (pin "4") (pinfunction "4_4") (pintype "passive"))
      (node (ref "X1") (pin "M1") (pinfunction "S1_M1") (pintype "passive"))
      (node (ref "X1") (pin "M2") (pinfunction "S2_M2") (pintype "passive"))
    )
    (net (code "48") (name "MIDI_OUT") (class "Default")
      (node (ref "R3") (pin "2") (pinfunction "2_2") (pintype "passive"))
      (node (ref "TENSY3.2") (pin "1") (pinfunction "1/TX1/T_1") (pintype "bidirectional"))
    )
    (net (code "49") (name "N$5") (class "Default")
      (node (ref "J32") (pin "P3") (pinfunction "3_P3") (pintype "passive"))
      (node (ref "TM16") (pin "B") (pinfunction "B_B") (pintype "passive"))
    )
    (net (code "50") (name "N$8") (class "Default")
      (node (ref "J28") (pin "P3") (pinfunction "3_P3") (pintype "passive"))
      (node (ref "TM15") (pin "B") (pinfunction "B_B") (pintype "passive"))
    )
    (net (code "51") (name "N$11") (class "Default")
      (node (ref "J24") (pin "P3") (pinfunction "3_P3") (pintype "passive"))
      (node (ref "TM14") (pin "B") (pinfunction "B_B") (pintype "passive"))
    )
    (net (code "52") (name "N$14") (class "Default")
      (node (ref "J20") (pin "P3") (pinfunction "3_P3") (pintype "passive"))
      (node (ref "TM13") (pin "B") (pinfunction "B_B") (pintype "passive"))
    )
    (net (code "53") (name "N$17") (class "Default")
      (node (ref "J16") (pin "P3") (pinfunction "3_P3") (pintype "passive"))
      (node (ref "TM12") (pin "B") (pinfunction "B_B") (pintype "passive"))
    )
    (net (code "54") (name "N$20") (class "Default")
      (node (ref "J12") (pin "P3") (pinfunction "3_P3") (pintype "passive"))
      (node (ref "TM11") (pin "B") (pinfunction "B_B") (pintype "passive"))
    )
    (net (code "55") (name "N$23") (class "Default")
      (node (ref "J8") (pin "P3") (pinfunction "3_P3") (pintype "passive"))
      (node (ref "TM10") (pin "B") (pinfunction "B_B") (pintype "passive"))
    )
    (net (code "56") (name "N$26") (class "Default")
      (node (ref "J4") (pin "P3") (pinfunction "3_P3") (pintype "passive"))
      (node (ref "TM9") (pin "B") (pinfunction "B_B") (pintype "passive"))
    )
    (net (code "57") (name "N$29") (class "Default")
      (node (ref "J31") (pin "P3") (pinfunction "3_P3") (pintype "passive"))
      (node (ref "TM8") (pin "B") (pinfunction "B_B") (pintype "passive"))
    )
    (net (code "58") (name "N$30") (class "Default")
      (node (ref "J27") (pin "P3") (pinfunction "3_P3") (pintype "passive"))
      (node (ref "TM7") (pin "B") (pinfunction "B_B") (pintype "passive"))
    )
    (net (code "59") (name "N$31") (class "Default")
      (node (ref "J23") (pin "P3") (pinfunction "3_P3") (pintype "passive"))
      (node (ref "TM6") (pin "B") (pinfunction "B_B") (pintype "passive"))
    )
    (net (code "60") (name "N$32") (class "Default")
      (node (ref "J19") (pin "P3") (pinfunction "3_P3") (pintype "passive"))
      (node (ref "TM5") (pin "B") (pinfunction "B_B") (pintype "passive"))
    )
    (net (code "61") (name "N$33") (class "Default")
      (node (ref "J15") (pin "P3") (pinfunction "3_P3") (pintype "passive"))
      (node (ref "TM4") (pin "B") (pinfunction "B_B") (pintype "passive"))
    )
    (net (code "62") (name "N$34") (class "Default")
      (node (ref "J11") (pin "P3") (pinfunction "3_P3") (pintype "passive"))
      (node (ref "TM3") (pin "B") (pinfunction "B_B") (pintype "passive"))
    )
    (net (code "63") (name "N$35") (class "Default")
      (node (ref "J7") (pin "P3") (pinfunction "3_P3") (pintype "passive"))
      (node (ref "TM2") (pin "B") (pinfunction "B_B") (pintype "passive"))
    )
    (net (code "64") (name "N$36") (class "Default")
      (node (ref "J3") (pin "P3") (pinfunction "3_P3") (pintype "passive"))
      (node (ref "TM1") (pin "B") (pinfunction "B_B") (pintype "passive"))
    )
    (net (code "65") (name "Net-(+5V-Pad3)") (class "Default")
      (node (ref "+5V") (pin "3") (pinfunction "3_3") (pintype "passive"))
      (node (ref "C21") (pin "+") (pinfunction "+_+") (pintype "passive"))
      (node (ref "SV1") (pin "11") (pinfunction "11_11") (pintype "passive"))
      (node (ref "SV1") (pin "12") (pinfunction "12_12") (pintype "passive"))
    )
    (net (code "66") (name "Net-(D4-PadA)") (class "Default")
      (node (ref "D4") (pin "A") (pinfunction "A_A") (pintype "passive"))
      (node (ref "SV1") (pin "10") (pinfunction "10_10") (pintype "passive"))
      (node (ref "SV1") (pin "9") (pinfunction "9_9") (pintype "passive"))
    )
    (net (code "67") (name "Net-(D5-PadC)") (class "Default")
      (node (ref "D5") (pin "C") (pinfunction "C_C") (pintype "passive"))
      (node (ref "SV1") (pin "1") (pinfunction "1_1") (pintype "passive"))
      (node (ref "SV1") (pin "2") (pinfunction "2_2") (pintype "passive"))
    )
    (net (code "68") (name "Net-(J2-2)") (class "Default")
      (node (ref "J2") (pin "P2") (pinfunction "2_P2") (pintype "passive"))
      (node (ref "JP1") (pin "4") (pinfunction "4_4") (pintype "passive"))
    )
    (net (code "69") (name "Net-(J2-3)") (class "Default")
      (node (ref "J2") (pin "P3") (pinfunction "3_P3") (pintype "passive"))
      (node (ref "JP1") (pin "3") (pinfunction "3_3") (pintype "passive"))
    )
    (net (code "70") (name "Net-(JP1-Pad1)") (class "Default")
      (node (ref "JP1") (pin "1") (pinfunction "1_1") (pintype "passive"))
      (node (ref "JP1") (pin "6") (pinfunction "6_6") (pintype "passive"))
      (node (ref "R4") (pin "1") (pinfunction "1_1") (pintype "passive"))
    )
    (net (code "71") (name "Net-(JP1-Pad2)") (class "Default")
      (node (ref "JP1") (pin "2") (pinfunction "2_2") (pintype "passive"))
      (node (ref "JP1") (pin "5") (pinfunction "5_5") (pintype "passive"))
      (node (ref "R3") (pin "1") (pinfunction "1_1") (pintype "passive"))
    )
    (net (code "72") (name "Net-(LED1-PadA)") (class "Default")
      (node (ref "LED1") (pin "A") (pinfunction "A_A") (pintype "passive"))
      (node (ref "R13") (pin "2") (pinfunction "2_2") (pintype "passive"))
    )
    (net (code "73") (name "Net-(LED2-PadA)") (class "Default")
      (node (ref "LED2") (pin "A") (pinfunction "A_A") (pintype "passive"))
      (node (ref "R9") (pin "2") (pinfunction "2_2") (pintype "passive"))
    )
    (net (code "74") (name "Net-(LED3-PadA)") (class "Default")
      (node (ref "LED3") (pin "A") (pinfunction "A_A") (pintype "passive"))
      (node (ref "R12") (pin "2") (pinfunction "2_2") (pintype "passive"))
    )
    (net (code "75") (name "Net-(LED4-PadA)") (class "Default")
      (node (ref "LED4") (pin "A") (pinfunction "A_A") (pintype "passive"))
      (node (ref "R11") (pin "2") (pinfunction "2_2") (pintype "passive"))
    )
    (net (code "76") (name "Net-(LED5-PadA)") (class "Default")
      (node (ref "LED5") (pin "A") (pinfunction "A_A") (pintype "passive"))
      (node (ref "R10") (pin "2") (pinfunction "2_2") (pintype "passive"))
    )
    (net (code "77") (name "Net-(LED6-PadA)") (class "Default")
      (node (ref "LED6") (pin "A") (pinfunction "A_A") (pintype "passive"))
      (node (ref "R14") (pin "2") (pinfunction "2_2") (pintype "passive"))
    )
    (net (code "78") (name "Net-(LED7-PadA)") (class "Default")
      (node (ref "LED7") (pin "A") (pinfunction "A_A") (pintype "passive"))
      (node (ref "R8") (pin "2") (pinfunction "2_2") (pintype "passive"))
    )
    (net (code "79") (name "Net-(LED8-PadA)") (class "Default")
      (node (ref "LED8") (pin "A") (pinfunction "A_A") (pintype "passive"))
      (node (ref "R7") (pin "2") (pinfunction "2_2") (pintype "passive"))
    )
    (net (code "80") (name "Net-(LED9-PadA)") (class "Default")
      (node (ref "LED9") (pin "A") (pinfunction "A_A") (pintype "passive"))
      (node (ref "R52") (pin "2") (pinfunction "2_2") (pintype "passive"))
    )
    (net (code "81") (name "Net-(LED10-PadA)") (class "Default")
      (node (ref "LED10") (pin "A") (pinfunction "A_A") (pintype "passive"))
      (node (ref "R51") (pin "2") (pinfunction "2_2") (pintype "passive"))
    )
    (net (code "82") (name "Net-(LED11-PadA)") (class "Default")
      (node (ref "LED11") (pin "A") (pinfunction "A_A") (pintype "passive"))
      (node (ref "R49") (pin "2") (pinfunction "2_2") (pintype "passive"))
    )
    (net (code "83") (name "Net-(LED12-PadA)") (class "Default")
      (node (ref "LED12") (pin "A") (pinfunction "A_A") (pintype "passive"))
      (node (ref "R50") (pin "2") (pinfunction "2_2") (pintype "passive"))
    )
    (net (code "84") (name "Net-(LED13-PadA)") (class "Default")
      (node (ref "LED13") (pin "A") (pinfunction "A_A") (pintype "passive"))
      (node (ref "R54") (pin "2") (pinfunction "2_2") (pintype "passive"))
    )
    (net (code "85") (name "Net-(LED14-PadA)") (class "Default")
      (node (ref "LED14") (pin "A") (pinfunction "A_A") (pintype "passive"))
      (node (ref "R53") (pin "2") (pinfunction "2_2") (pintype "passive"))
    )
    (net (code "86") (name "Net-(LED15-PadA)") (class "Default")
      (node (ref "LED15") (pin "A") (pinfunction "A_A") (pintype "passive"))
      (node (ref "R48") (pin "2") (pinfunction "2_2") (pintype "passive"))
    )
    (net (code "87") (name "Net-(LED16-PadA)") (class "Default")
      (node (ref "LED16") (pin "A") (pinfunction "A_A") (pintype "passive"))
      (node (ref "R47") (pin "2") (pinfunction "2_2") (pintype "passive"))
    )
    (net (code "88") (name "Net-(U1A--IN)") (class "Default")
      (node (ref "R26") (pin "2") (pinfunction "2_2") (pintype "passive"))
      (node (ref "R28") (pin "2") (pinfunction "2_2") (pintype "passive"))
      (node (ref "R32") (pin "1") (pinfunction "1_1") (pintype "passive"))
      (node (ref "U1") (pin "2") (pinfunction "-IN_2") (pintype "input"))
    )
    (net (code "89") (name "Net-(U1B--IN)") (class "Default")
      (node (ref "R16") (pin "1") (pinfunction "1_1") (pintype "passive"))
      (node (ref "R20") (pin "2") (pinfunction "2_2") (pintype "passive"))
      (node (ref "R24") (pin "2") (pinfunction "2_2") (pintype "passive"))
      (node (ref "U1") (pin "6") (pinfunction "-IN_6") (pintype "input"))
    )
    (net (code "90") (name "Net-(U1C--IN)") (class "Default")
      (node (ref "R15") (pin "1") (pinfunction "1_1") (pintype "passive"))
      (node (ref "R19") (pin "2") (pinfunction "2_2") (pintype "passive"))
      (node (ref "R23") (pin "2") (pinfunction "2_2") (pintype "passive"))
      (node (ref "U1") (pin "9") (pinfunction "-IN_9") (pintype "input"))
    )
    (net (code "91") (name "Net-(U1D--IN)") (class "Default")
      (node (ref "R25") (pin "2") (pinfunction "2_2") (pintype "passive"))
      (node (ref "R27") (pin "2") (pinfunction "2_2") (pintype "passive"))
      (node (ref "R31") (pin "1") (pinfunction "1_1") (pintype "passive"))
      (node (ref "U1") (pin "13") (pinfunction "-IN_13") (pintype "input"))
    )
    (net (code "92") (name "Net-(U2A--IN)") (class "Default")
      (node (ref "R38") (pin "2") (pinfunction "2_2") (pintype "passive"))
      (node (ref "R40") (pin "2") (pinfunction "2_2") (pintype "passive"))
      (node (ref "R41") (pin "1") (pinfunction "1_1") (pintype "passive"))
      (node (ref "U2") (pin "2") (pinfunction "-IN_2") (pintype "input"))
    )
    (net (code "93") (name "Net-(U2B--IN)") (class "Default")
      (node (ref "R30") (pin "1") (pinfunction "1_1") (pintype "passive"))
      (node (ref "R34") (pin "2") (pinfunction "2_2") (pintype "passive"))
      (node (ref "R36") (pin "2") (pinfunction "2_2") (pintype "passive"))
      (node (ref "U2") (pin "6") (pinfunction "-IN_6") (pintype "input"))
    )
    (net (code "94") (name "Net-(U2C--IN)") (class "Default")
      (node (ref "R29") (pin "1") (pinfunction "1_1") (pintype "passive"))
      (node (ref "R33") (pin "2") (pinfunction "2_2") (pintype "passive"))
      (node (ref "R35") (pin "2") (pinfunction "2_2") (pintype "passive"))
      (node (ref "U2") (pin "9") (pinfunction "-IN_9") (pintype "input"))
    )
    (net (code "95") (name "Net-(U2D--IN)") (class "Default")
      (node (ref "R37") (pin "2") (pinfunction "2_2") (pintype "passive"))
      (node (ref "R39") (pin "2") (pinfunction "2_2") (pintype "passive"))
      (node (ref "R42") (pin "1") (pinfunction "1_1") (pintype "passive"))
      (node (ref "U2") (pin "13") (pinfunction "-IN_13") (pintype "input"))
    )
    (net (code "96") (name "Net-(U3A--IN)") (class "Default")
      (node (ref "R13") (pin "1") (pinfunction "1_1") (pintype "passive"))
      (node (ref "R2") (pin "1") (pinfunction "1_1") (pintype "passive"))
      (node (ref "U3") (pin "1") (pinfunction "OUT_1") (pintype "output"))
      (node (ref "U3") (pin "2") (pinfunction "-IN_2") (pintype "input"))
    )
    (net (code "97") (name "Net-(U3B--IN)") (class "Default")
      (node (ref "R18") (pin "1") (pinfunction "1_1") (pintype "passive"))
      (node (ref "R9") (pin "1") (pinfunction "1_1") (pintype "passive"))
      (node (ref "U3") (pin "6") (pinfunction "-IN_6") (pintype "input"))
      (node (ref "U3") (pin "7") (pinfunction "OUT_7") (pintype "output"))
    )
    (net (code "98") (name "Net-(U3C--IN)") (class "Default")
      (node (ref "R12") (pin "1") (pinfunction "1_1") (pintype "passive"))
      (node (ref "R22") (pin "1") (pinfunction "1_1") (pintype "passive"))
      (node (ref "U3") (pin "8") (pinfunction "OUT_8") (pintype "output"))
      (node (ref "U3") (pin "9") (pinfunction "-IN_9") (pintype "input"))
    )
    (net (code "99") (name "Net-(U3D--IN)") (class "Default")
      (node (ref "R11") (pin "1") (pinfunction "1_1") (pintype "passive"))
      (node (ref "R44") (pin "1") (pinfunction "1_1") (pintype "passive"))
      (node (ref "U3") (pin "13") (pinfunction "-IN_13") (pintype "input"))
      (node (ref "U3") (pin "14") (pinfunction "OUT_14") (pintype "output"))
    )
    (net (code "100") (name "Net-(U4A--IN)") (class "Default")
      (node (ref "R10") (pin "1") (pinfunction "1_1") (pintype "passive"))
      (node (ref "R46") (pin "1") (pinfunction "1_1") (pintype "passive"))
      (node (ref "U4") (pin "1") (pinfunction "OUT_1") (pintype "output"))
      (node (ref "U4") (pin "2") (pinfunction "-IN_2") (pintype "input"))
    )
    (net (code "101") (name "Net-(U4B--IN)") (class "Default")
      (node (ref "R14") (pin "1") (pinfunction "1_1") (pintype "passive"))
      (node (ref "R58") (pin "1") (pinfunction "1_1") (pintype "passive"))
      (node (ref "U4") (pin "6") (pinfunction "-IN_6") (pintype "input"))
      (node (ref "U4") (pin "7") (pinfunction "OUT_7") (pintype "output"))
    )
    (net (code "102") (name "Net-(U4C--IN)") (class "Default")
      (node (ref "R62") (pin "1") (pinfunction "1_1") (pintype "passive"))
      (node (ref "R8") (pin "1") (pinfunction "1_1") (pintype "passive"))
      (node (ref "U4") (pin "8") (pinfunction "OUT_8") (pintype "output"))
      (node (ref "U4") (pin "9") (pinfunction "-IN_9") (pintype "input"))
    )
    (net (code "103") (name "Net-(U4D--IN)") (class "Default")
      (node (ref "R7") (pin "1") (pinfunction "1_1") (pintype "passive"))
      (node (ref "R77") (pin "1") (pinfunction "1_1") (pintype "passive"))
      (node (ref "U4") (pin "13") (pinfunction "-IN_13") (pintype "input"))
      (node (ref "U4") (pin "14") (pinfunction "OUT_14") (pintype "output"))
    )
    (net (code "104") (name "Net-(U6A--IN)") (class "Default")
      (node (ref "R1") (pin "1") (pinfunction "1_1") (pintype "passive"))
      (node (ref "R52") (pin "1") (pinfunction "1_1") (pintype "passive"))
      (node (ref "U6") (pin "1") (pinfunction "OUT_1") (pintype "output"))
      (node (ref "U6") (pin "2") (pinfunction "-IN_2") (pintype "input"))
    )
    (net (code "105") (name "Net-(U6B--IN)") (class "Default")
      (node (ref "R17") (pin "1") (pinfunction "1_1") (pintype "passive"))
      (node (ref "R51") (pin "1") (pinfunction "1_1") (pintype "passive"))
      (node (ref "U6") (pin "6") (pinfunction "-IN_6") (pintype "input"))
      (node (ref "U6") (pin "7") (pinfunction "OUT_7") (pintype "output"))
    )
    (net (code "106") (name "Net-(U6C--IN)") (class "Default")
      (node (ref "R21") (pin "1") (pinfunction "1_1") (pintype "passive"))
      (node (ref "R49") (pin "1") (pinfunction "1_1") (pintype "passive"))
      (node (ref "U6") (pin "8") (pinfunction "OUT_8") (pintype "output"))
      (node (ref "U6") (pin "9") (pinfunction "-IN_9") (pintype "input"))
    )
    (net (code "107") (name "Net-(U6D--IN)") (class "Default")
      (node (ref "R43") (pin "1") (pinfunction "1_1") (pintype "passive"))
      (node (ref "R50") (pin "1") (pinfunction "1_1") (pintype "passive"))
      (node (ref "U6") (pin "13") (pinfunction "-IN_13") (pintype "input"))
      (node (ref "U6") (pin "14") (pinfunction "OUT_14") (pintype "output"))
    )
    (net (code "108") (name "Net-(U7A--IN)") (class "Default")
      (node (ref "R66") (pin "2") (pinfunction "2_2") (pintype "passive"))
      (node (ref "R68") (pin "2") (pinfunction "2_2") (pintype "passive"))
      (node (ref "R70") (pin "1") (pinfunction "1_1") (pintype "passive"))
      (node (ref "U7") (pin "2") (pinfunction "-IN_2") (pintype "input"))
    )
    (net (code "109") (name "Net-(U7B--IN)") (class "Default")
      (node (ref "R56") (pin "1") (pinfunction "1_1") (pintype "passive"))
      (node (ref "R60") (pin "2") (pinfunction "2_2") (pintype "passive"))
      (node (ref "R64") (pin "2") (pinfunction "2_2") (pintype "passive"))
      (node (ref "U7") (pin "6") (pinfunction "-IN_6") (pintype "input"))
    )
    (net (code "110") (name "Net-(U7C--IN)") (class "Default")
      (node (ref "R55") (pin "1") (pinfunction "1_1") (pintype "passive"))
      (node (ref "R59") (pin "2") (pinfunction "2_2") (pintype "passive"))
      (node (ref "R63") (pin "2") (pinfunction "2_2") (pintype "passive"))
      (node (ref "U7") (pin "9") (pinfunction "-IN_9") (pintype "input"))
    )
    (net (code "111") (name "Net-(U7D--IN)") (class "Default")
      (node (ref "R65") (pin "2") (pinfunction "2_2") (pintype "passive"))
      (node (ref "R67") (pin "2") (pinfunction "2_2") (pintype "passive"))
      (node (ref "R69") (pin "1") (pinfunction "1_1") (pintype "passive"))
      (node (ref "U7") (pin "13") (pinfunction "-IN_13") (pintype "input"))
    )
    (net (code "112") (name "Net-(U8A--IN)") (class "Default")
      (node (ref "R80") (pin "2") (pinfunction "2_2") (pintype "passive"))
      (node (ref "R82") (pin "2") (pinfunction "2_2") (pintype "passive"))
      (node (ref "R84") (pin "1") (pinfunction "1_1") (pintype "passive"))
      (node (ref "U8") (pin "2") (pinfunction "-IN_2") (pintype "input"))
    )
    (net (code "113") (name "Net-(U8B--IN)") (class "Default")
      (node (ref "R72") (pin "1") (pinfunction "1_1") (pintype "passive"))
      (node (ref "R74") (pin "2") (pinfunction "2_2") (pintype "passive"))
      (node (ref "R78") (pin "2") (pinfunction "2_2") (pintype "passive"))
      (node (ref "U8") (pin "6") (pinfunction "-IN_6") (pintype "input"))
    )
    (net (code "114") (name "Net-(U8C--IN)") (class "Default")
      (node (ref "R71") (pin "1") (pinfunction "1_1") (pintype "passive"))
      (node (ref "R73") (pin "2") (pinfunction "2_2") (pintype "passive"))
      (node (ref "R75") (pin "2") (pinfunction "2_2") (pintype "passive"))
      (node (ref "U8") (pin "9") (pinfunction "-IN_9") (pintype "input"))
    )
    (net (code "115") (name "Net-(U8D--IN)") (class "Default")
      (node (ref "R79") (pin "2") (pinfunction "2_2") (pintype "passive"))
      (node (ref "R81") (pin "2") (pinfunction "2_2") (pintype "passive"))
      (node (ref "R83") (pin "1") (pinfunction "1_1") (pintype "passive"))
      (node (ref "U8") (pin "13") (pinfunction "-IN_13") (pintype "input"))
    )
    (net (code "116") (name "Net-(U9A--IN)") (class "Default")
      (node (ref "R45") (pin "1") (pinfunction "1_1") (pintype "passive"))
      (node (ref "R54") (pin "1") (pinfunction "1_1") (pintype "passive"))
      (node (ref "U9") (pin "1") (pinfunction "OUT_1") (pintype "output"))
      (node (ref "U9") (pin "2") (pinfunction "-IN_2") (pintype "input"))
    )
    (net (code "117") (name "Net-(U9B--IN)") (class "Default")
      (node (ref "R53") (pin "1") (pinfunction "1_1") (pintype "passive"))
      (node (ref "R57") (pin "1") (pinfunction "1_1") (pintype "passive"))
      (node (ref "U9") (pin "6") (pinfunction "-IN_6") (pintype "input"))
      (node (ref "U9") (pin "7") (pinfunction "OUT_7") (pintype "output"))
    )
    (net (code "118") (name "Net-(U9C--IN)") (class "Default")
      (node (ref "R48") (pin "1") (pinfunction "1_1") (pintype "passive"))
      (node (ref "R61") (pin "1") (pinfunction "1_1") (pintype "passive"))
      (node (ref "U9") (pin "8") (pinfunction "OUT_8") (pintype "output"))
      (node (ref "U9") (pin "9") (pinfunction "-IN_9") (pintype "input"))
    )
    (net (code "119") (name "Net-(U9D--IN)") (class "Default")
      (node (ref "R47") (pin "1") (pinfunction "1_1") (pintype "passive"))
      (node (ref "R76") (pin "1") (pinfunction "1_1") (pintype "passive"))
      (node (ref "U9") (pin "13") (pinfunction "-IN_13") (pintype "input"))
      (node (ref "U9") (pin "14") (pinfunction "OUT_14") (pintype "output"))
    )
    (net (code "120") (name "S0") (class "Default")
      (node (ref "TENSY3.2") (pin "8") (pinfunction "8/TX3_8") (pintype "bidirectional"))
      (node (ref "U5") (pin "10") (pinfunction "S0_10") (pintype "input"))
    )
    (net (code "121") (name "S1") (class "Default")
      (node (ref "TENSY3.2") (pin "7") (pinfunction "7/RX3_7") (pintype "bidirectional"))
      (node (ref "U5") (pin "11") (pinfunction "S1_11") (pintype "input"))
    )
    (net (code "122") (name "S2") (class "Default")
      (node (ref "TENSY3.2") (pin "6") (pinfunction "6/PWM_6") (pintype "bidirectional"))
      (node (ref "U5") (pin "14") (pinfunction "S2_14") (pintype "input"))
    )
    (net (code "123") (name "S3") (class "Default")
      (node (ref "TENSY3.2") (pin "5") (pinfunction "5/PWM_5") (pintype "bidirectional"))
      (node (ref "U5") (pin "13") (pinfunction "S3_13") (pintype "input"))
    )
    (net (code "124") (name "SCL") (class "Default")
      (node (ref "D3") (pin "C") (pinfunction "C_C") (pintype "passive"))
      (node (ref "D6") (pin "A") (pinfunction "A_A") (pintype "passive"))
      (node (ref "J1") (pin "P2") (pinfunction "2_P2") (pintype "passive"))
      (node (ref "JP3") (pin "2") (pinfunction "2_2") (pintype "passive"))
      (node (ref "TENSY3.2") (pin "19/A5") (pinfunction "19/A5/T/SCL0_19/A5") (pintype "bidirectional"))
    )
    (net (code "125") (name "SDA") (class "Default")
      (node (ref "D1") (pin "A") (pinfunction "A_A") (pintype "passive"))
      (node (ref "D2") (pin "C") (pinfunction "C_C") (pintype "passive"))
      (node (ref "J1") (pin "P3") (pinfunction "3_P3") (pintype "passive"))
      (node (ref "JP3") (pin "3") (pinfunction "3_3") (pintype "passive"))
      (node (ref "TENSY3.2") (pin "18/A4") (pinfunction "18/A4/T/SDA0_18/A4") (pintype "bidirectional"))
    )
    (net (code "126") (name "VCC") (class "Default")
      (node (ref "C11") (pin "1") (pinfunction "1_1") (pintype "passive"))
      (node (ref "C14") (pin "1") (pinfunction "1_1") (pintype "passive"))
      (node (ref "C16") (pin "1") (pinfunction "1_1") (pintype "passive"))
      (node (ref "C20") (pin "1") (pinfunction "1_1") (pintype "passive"))
      (node (ref "C23") (pin "1") (pinfunction "1_1") (pintype "passive"))
      (node (ref "C3") (pin "+") (pinfunction "+_+") (pintype "passive"))
      (node (ref "C6") (pin "+") (pinfunction "+_+") (pintype "passive"))
      (node (ref "D4") (pin "C") (pinfunction "C_C") (pintype "passive"))
      (node (ref "IC3") (pin "3") (pinfunction "VIN_3") (pintype "input"))
      (node (ref "IC4") (pin "1") (pinfunction "VI_1") (pintype "input"))
      (node (ref "U3") (pin "4") (pinfunction "V+_4") (pintype "power_in"))
      (node (ref "U4") (pin "4") (pinfunction "V+_4") (pintype "power_in"))
      (node (ref "U6") (pin "4") (pinfunction "V+_4") (pintype "power_in"))
      (node (ref "U9") (pin "4") (pinfunction "V+_4") (pintype "power_in"))
    )
    (net (code "127") (name "VEE") (class "Default")
      (node (ref "C10") (pin "1") (pinfunction "1_1") (pintype "passive"))
      (node (ref "C13") (pin "1") (pinfunction "1_1") (pintype "passive"))
      (node (ref "C15") (pin "1") (pinfunction "1_1") (pintype "passive"))
      (node (ref "C19") (pin "1") (pinfunction "1_1") (pintype "passive"))
      (node (ref "C4") (pin "-") (pinfunction "-_-") (pintype "passive"))
      (node (ref "D5") (pin "A") (pinfunction "A_A") (pintype "passive"))
      (node (ref "R5") (pin "1") (pinfunction "1_1") (pintype "passive"))
      (node (ref "R6") (pin "1") (pinfunction "1_1") (pintype "passive"))
      (node (ref "U3") (pin "11") (pinfunction "V-_11") (pintype "power_in"))
      (node (ref "U4") (pin "11") (pinfunction "V-_11") (pintype "power_in"))
      (node (ref "U6") (pin "11") (pinfunction "V-_11") (pintype "power_in"))
      (node (ref "U9") (pin "11") (pinfunction "V-_11") (pintype "power_in"))
    )
    (net (code "128") (name "W0") (class "Default")
      (node (ref "R26") (pin "1") (pinfunction "1_1") (pintype "passive"))
      (node (ref "TM1") (pin "WIPER") (pinfunction "WIPER_WIPER") (pintype "passive"))
      (node (ref "U3") (pin "3") (pinfunction "+IN_3") (pintype "input"))
    )
    (net (code "129") (name "W1") (class "Default")
      (node (ref "R24") (pin "1") (pinfunction "1_1") (pintype "passive"))
      (node (ref "TM2") (pin "WIPER") (pinfunction "WIPER_WIPER") (pintype "passive"))
      (node (ref "U3") (pin "5") (pinfunction "+IN_5") (pintype "input"))
    )
    (net (code "130") (name "W2") (class "Default")
      (node (ref "R23") (pin "1") (pinfunction "1_1") (pintype "passive"))
      (node (ref "TM3") (pin "WIPER") (pinfunction "WIPER_WIPER") (pintype "passive"))
      (node (ref "U3") (pin "10") (pinfunction "+IN_10") (pintype "input"))
    )
    (net (code "131") (name "W3") (class "Default")
      (node (ref "R25") (pin "1") (pinfunction "1_1") (pintype "passive"))
      (node (ref "TM4") (pin "WIPER") (pinfunction "WIPER_WIPER") (pintype "passive"))
      (node (ref "U3") (pin "12") (pinfunction "+IN_12") (pintype "input"))
    )
    (net (code "132") (name "W4") (class "Default")
      (node (ref "R38") (pin "1") (pinfunction "1_1") (pintype "passive"))
      (node (ref "TM5") (pin "WIPER") (pinfunction "WIPER_WIPER") (pintype "passive"))
      (node (ref "U4") (pin "3") (pinfunction "+IN_3") (pintype "input"))
    )
    (net (code "133") (name "W5") (class "Default")
      (node (ref "R36") (pin "1") (pinfunction "1_1") (pintype "passive"))
      (node (ref "TM6") (pin "WIPER") (pinfunction "WIPER_WIPER") (pintype "passive"))
      (node (ref "U4") (pin "5") (pinfunction "+IN_5") (pintype "input"))
    )
    (net (code "134") (name "W6") (class "Default")
      (node (ref "R35") (pin "1") (pinfunction "1_1") (pintype "passive"))
      (node (ref "TM7") (pin "WIPER") (pinfunction "WIPER_WIPER") (pintype "passive"))
      (node (ref "U4") (pin "10") (pinfunction "+IN_10") (pintype "input"))
    )
    (net (code "135") (name "W7") (class "Default")
      (node (ref "R37") (pin "1") (pinfunction "1_1") (pintype "passive"))
      (node (ref "TM8") (pin "WIPER") (pinfunction "WIPER_WIPER") (pintype "passive"))
      (node (ref "U4") (pin "12") (pinfunction "+IN_12") (pintype "input"))
    )
    (net (code "136") (name "W8") (class "Default")
      (node (ref "R66") (pin "1") (pinfunction "1_1") (pintype "passive"))
      (node (ref "TM9") (pin "WIPER") (pinfunction "WIPER_WIPER") (pintype "passive"))
      (node (ref "U6") (pin "3") (pinfunction "+IN_3") (pintype "input"))
    )
    (net (code "137") (name "W9") (class "Default")
      (node (ref "R64") (pin "1") (pinfunction "1_1") (pintype "passive"))
      (node (ref "TM10") (pin "WIPER") (pinfunction "WIPER_WIPER") (pintype "passive"))
      (node (ref "U6") (pin "5") (pinfunction "+IN_5") (pintype "input"))
    )
    (net (code "138") (name "W10") (class "Default")
      (node (ref "R63") (pin "1") (pinfunction "1_1") (pintype "passive"))
      (node (ref "TM11") (pin "WIPER") (pinfunction "WIPER_WIPER") (pintype "passive"))
      (node (ref "U6") (pin "10") (pinfunction "+IN_10") (pintype "input"))
    )
    (net (code "139") (name "W11") (class "Default")
      (node (ref "R65") (pin "1") (pinfunction "1_1") (pintype "passive"))
      (node (ref "TM12") (pin "WIPER") (pinfunction "WIPER_WIPER") (pintype "passive"))
      (node (ref "U6") (pin "12") (pinfunction "+IN_12") (pintype "input"))
    )
    (net (code "140") (name "W12") (class "Default")
      (node (ref "R80") (pin "1") (pinfunction "1_1") (pintype "passive"))
      (node (ref "TM13") (pin "WIPER") (pinfunction "WIPER_WIPER") (pintype "passive"))
      (node (ref "U9") (pin "3") (pinfunction "+IN_3") (pintype "input"))
    )
    (net (code "141") (name "W13") (class "Default")
      (node (ref "R78") (pin "1") (pinfunction "1_1") (pintype "passive"))
      (node (ref "TM14") (pin "WIPER") (pinfunction "WIPER_WIPER") (pintype "passive"))
      (node (ref "U9") (pin "5") (pinfunction "+IN_5") (pintype "input"))
    )
    (net (code "142") (name "W14") (class "Default")
      (node (ref "R75") (pin "1") (pinfunction "1_1") (pintype "passive"))
      (node (ref "TM15") (pin "WIPER") (pinfunction "WIPER_WIPER") (pintype "passive"))
      (node (ref "U9") (pin "10") (pinfunction "+IN_10") (pintype "input"))
    )
    (net (code "143") (name "W15") (class "Default")
      (node (ref "R79") (pin "1") (pinfunction "1_1") (pintype "passive"))
      (node (ref "TM16") (pin "WIPER") (pinfunction "WIPER_WIPER") (pintype "passive"))
      (node (ref "U9") (pin "12") (pinfunction "+IN_12") (pintype "input"))
    )
    (net (code "144") (name "unconnected-(J5-2-PadP2)") (class "Default")
      (node (ref "J5") (pin "P2") (pinfunction "2_P2") (pintype "passive"))
    )
    (net (code "145") (name "unconnected-(J6-2-PadP2)") (class "Default")
      (node (ref "J6") (pin "P2") (pinfunction "2_P2") (pintype "passive"))
    )
    (net (code "146") (name "unconnected-(J9-2-PadP2)") (class "Default")
      (node (ref "J9") (pin "P2") (pinfunction "2_P2") (pintype "passive"))
    )
    (net (code "147") (name "unconnected-(J10-2-PadP2)") (class "Default")
      (node (ref "J10") (pin "P2") (pinfunction "2_P2") (pintype "passive"))
    )
    (net (code "148") (name "unconnected-(J13-2-PadP2)") (class "Default")
      (node (ref "J13") (pin "P2") (pinfunction "2_P2") (pintype "passive"))
    )
    (net (code "149") (name "unconnected-(J14-2-PadP2)") (class "Default")
      (node (ref "J14") (pin "P2") (pinfunction "2_P2") (pintype "passive"))
    )
    (net (code "150") (name "unconnected-(J17-2-PadP2)") (class "Default")
      (node (ref "J17") (pin "P2") (pinfunction "2_P2") (pintype "passive"))
    )
    (net (code "151") (name "unconnected-(J18-2-PadP2)") (class "Default")
      (node (ref "J18") (pin "P2") (pinfunction "2_P2") (pintype "passive"))
    )
    (net (code "152") (name "unconnected-(J21-2-PadP2)") (class "Default")
      (node (ref "J21") (pin "P2") (pinfunction "2_P2") (pintype "passive"))
    )
    (net (code "153") (name "unconnected-(J22-2-PadP2)") (class "Default")
      (node (ref "J22") (pin "P2") (pinfunction "2_P2") (pintype "passive"))
    )
    (net (code "154") (name "unconnected-(J25-2-PadP2)") (class "Default")
      (node (ref "J25") (pin "P2") (pinfunction "2_P2") (pintype "passive"))
    )
    (net (code "155") (name "unconnected-(J26-2-PadP2)") (class "Default")
      (node (ref "J26") (pin "P2") (pinfunction "2_P2") (pintype "passive"))
    )
    (net (code "156") (name "unconnected-(J29-2-PadP2)") (class "Default")
      (node (ref "J29") (pin "P2") (pinfunction "2_P2") (pintype "passive"))
    )
    (net (code "157") (name "unconnected-(J30-2-PadP2)") (class "Default")
      (node (ref "J30") (pin "P2") (pinfunction "2_P2") (pintype "passive"))
    )
    (net (code "158") (name "unconnected-(J33-2-PadP2)") (class "Default")
      (node (ref "J33") (pin "P2") (pinfunction "2_P2") (pintype "passive"))
    )
    (net (code "159") (name "unconnected-(J34-2-PadP2)") (class "Default")
      (node (ref "J34") (pin "P2") (pinfunction "2_P2") (pintype "passive"))
    )
    (net (code "160") (name "unconnected-(SV1-Pad13)") (class "Default")
      (node (ref "SV1") (pin "13") (pinfunction "13_13") (pintype "passive"))
    )
    (net (code "161") (name "unconnected-(SV1-Pad14)") (class "Default")
      (node (ref "SV1") (pin "14") (pinfunction "14_14") (pintype "passive"))
    )
    (net (code "162") (name "unconnected-(SV1-Pad15)") (class "Default")
      (node (ref "SV1") (pin "15") (pinfunction "15_15") (pintype "passive"))
    )
    (net (code "163") (name "unconnected-(SV1-Pad16)") (class "Default")
      (node (ref "SV1") (pin "16") (pinfunction "16_16") (pintype "passive"))
    )
    (net (code "164") (name "unconnected-(TENSY3.2-0{slash}RX1{slash}T-Pad0)") (class "Default")
      (node (ref "TENSY3.2") (pin "0") (pinfunction "0/RX1/T_0") (pintype "bidirectional"))
    )
    (net (code "165") (name "unconnected-(TENSY3.2-3{slash}CAN-TX{slash}PWM-Pad3)") (class "Default")
      (node (ref "TENSY3.2") (pin "3") (pinfunction "3/CAN-TX/PWM_3") (pintype "bidirectional"))
    )
    (net (code "166") (name "unconnected-(TENSY3.2-4{slash}CAN-RX{slash}PWM-Pad4)") (class "Default")
      (node (ref "TENSY3.2") (pin "4") (pinfunction "4/CAN-RX/PWM_4") (pintype "bidirectional"))
    )
    (net (code "167") (name "unconnected-(TENSY3.2-9{slash}RX2{slash}PWM-Pad9)") (class "Default")
      (node (ref "TENSY3.2") (pin "9") (pinfunction "9/RX2/PWM_9") (pintype "bidirectional"))
    )
    (net (code "168") (name "unconnected-(TENSY3.2-10{slash}TX2{slash}PWM-Pad10)") (class "Default")
      (node (ref "TENSY3.2") (pin "10") (pinfunction "10/TX2/PWM_10") (pintype "bidirectional"))
    )
    (net (code "169") (name "unconnected-(TENSY3.2-11{slash}MOSI-Pad11)") (class "Default")
      (node (ref "TENSY3.2") (pin "11") (pinfunction "11/MOSI_11") (pintype "bidirectional"))
    )
    (net (code "170") (name "unconnected-(TENSY3.2-12{slash}MISO-Pad12)") (class "Default")
      (node (ref "TENSY3.2") (pin "12") (pinfunction "12/MISO_12") (pintype "bidirectional"))
    )
    (net (code "171") (name "unconnected-(TENSY3.2-13{slash}SCK{slash}LED-Pad13)") (class "Default")
      (node (ref "TENSY3.2") (pin "13") (pinfunction "13/SCK/LED_13") (pintype "bidirectional"))
    )
    (net (code "172") (name "unconnected-(TENSY3.2-15{slash}A1{slash}T-Pad15{slash}A1)") (class "Default")
      (node (ref "TENSY3.2") (pin "15/A1") (pinfunction "15/A1/T_15/A1") (pintype "bidirectional"))
    )
    (net (code "173") (name "unconnected-(TENSY3.2-16{slash}A2{slash}T-Pad16{slash}A2)") (class "Default")
      (node (ref "TENSY3.2") (pin "16/A2") (pinfunction "16/A2/T_16/A2") (pintype "bidirectional"))
    )
    (net (code "174") (name "unconnected-(TENSY3.2-17{slash}A3{slash}T-Pad17{slash}A3)") (class "Default")
      (node (ref "TENSY3.2") (pin "17/A3") (pinfunction "17/A3/T_17/A3") (pintype "bidirectional"))
    )
    (net (code "175") (name "unconnected-(TENSY3.2-20{slash}A6{slash}PWM-Pad20{slash}A6)") (class "Default")
      (node (ref "TENSY3.2") (pin "20/A6") (pinfunction "20/A6/PWM_20/A6") (pintype "bidirectional"))
    )
    (net (code "176") (name "unconnected-(TENSY3.2-21{slash}A7{slash}PWM-Pad21{slash}A7)") (class "Default")
      (node (ref "TENSY3.2") (pin "21/A7") (pinfunction "21/A7/PWM_21/A7") (pintype "bidirectional"))
    )
    (net (code "177") (name "unconnected-(TENSY3.2-22{slash}A8{slash}T{slash}PWM-Pad22{slash}A8)") (class "Default")
      (node (ref "TENSY3.2") (pin "22/A8") (pinfunction "22/A8/T/PWM_22/A8") (pintype "bidirectional"))
    )
    (net (code "178") (name "unconnected-(TENSY3.2-23{slash}A9{slash}T{slash}PWM-Pad23{slash}A9)") (class "Default")
      (node (ref "TENSY3.2") (pin "23/A9") (pinfunction "23/A9/T/PWM_23/A9") (pintype "bidirectional"))
    )
    (net (code "179") (name "unconnected-(TENSY3.2-Pad2)") (class "Default")
      (node (ref "TENSY3.2") (pin "2") (pinfunction "2_2") (pintype "bidirectional"))
    )
  )
)
